# Power_Supply.net
KiCad netlist of a schematic drawn in Altium Designer
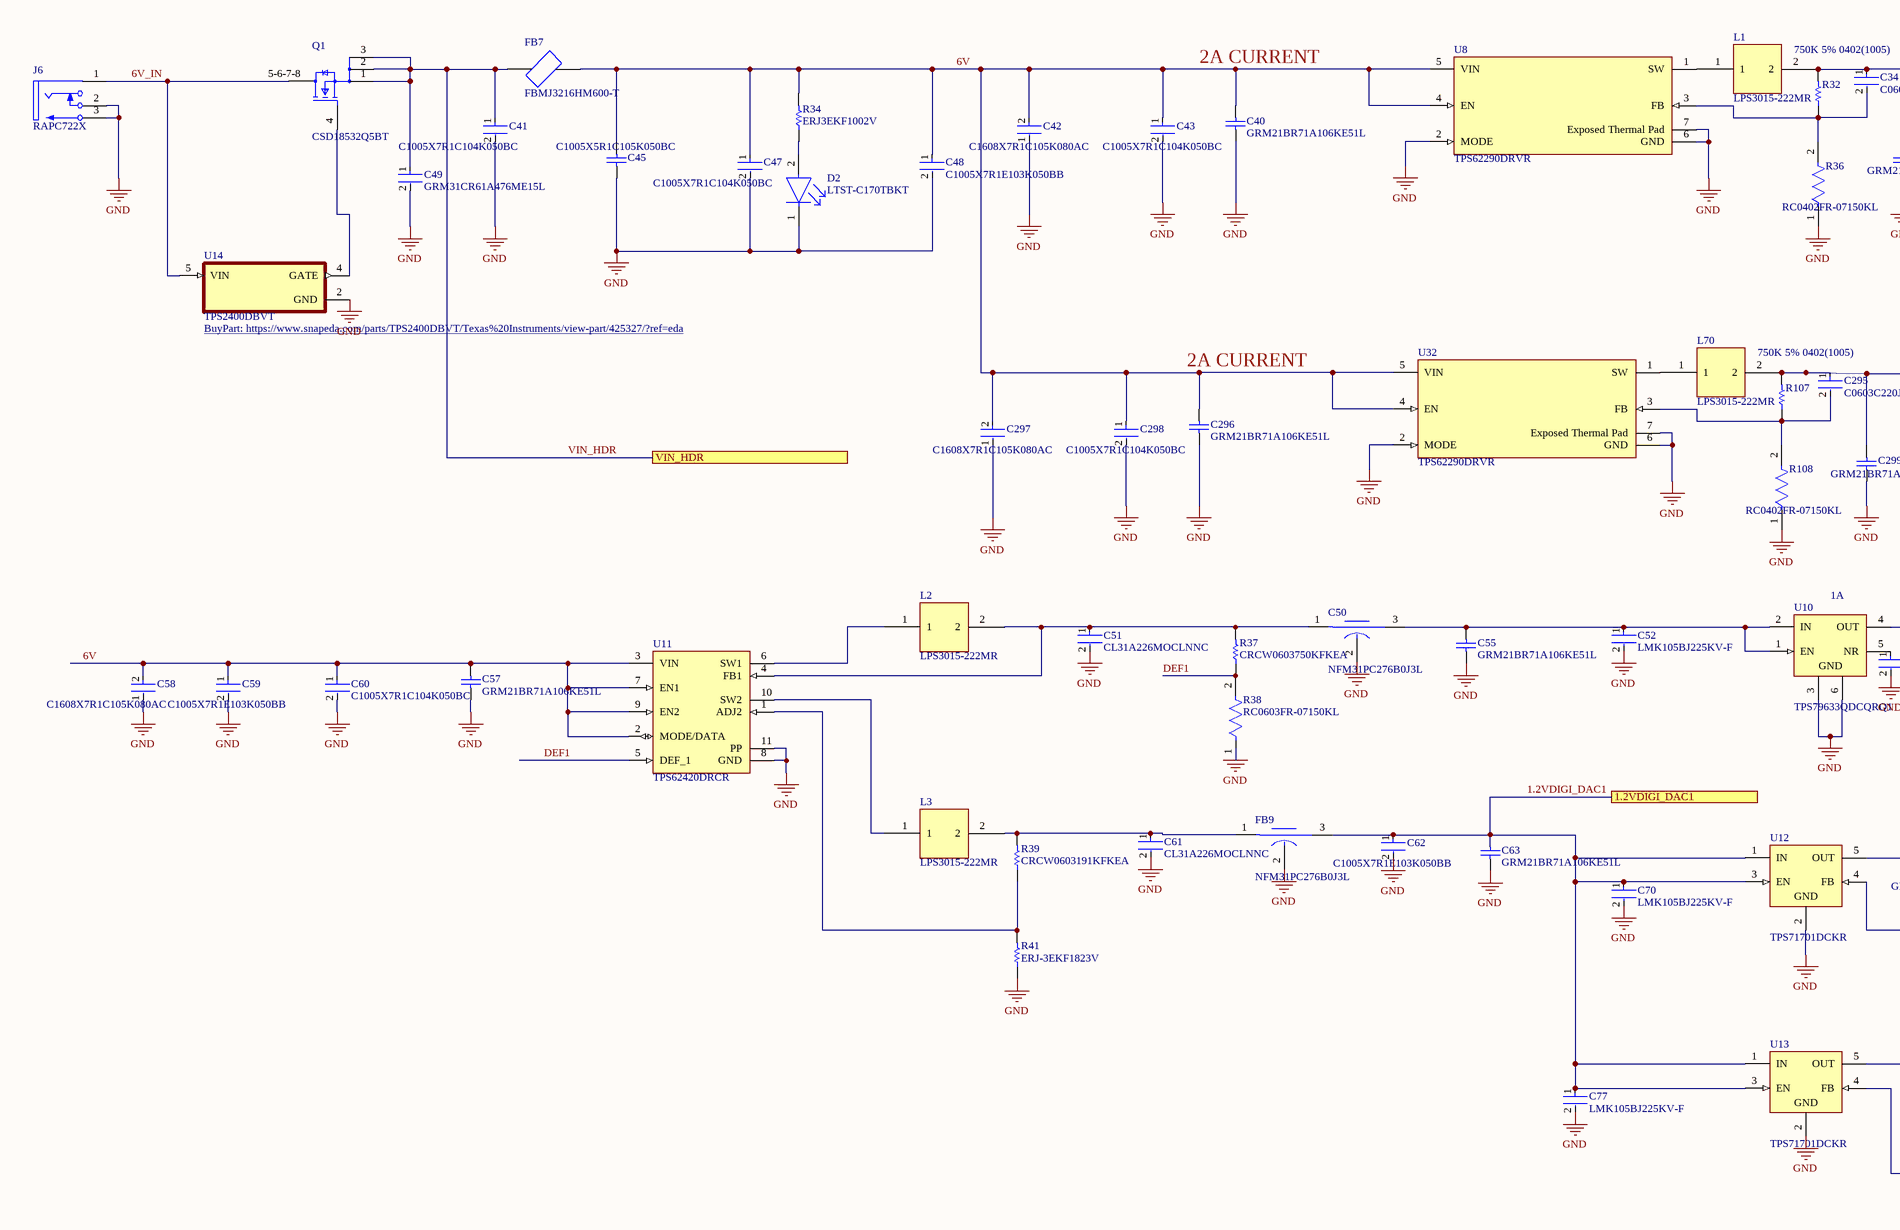
[diagram p0: Power_Supply.SchDoc, top left]
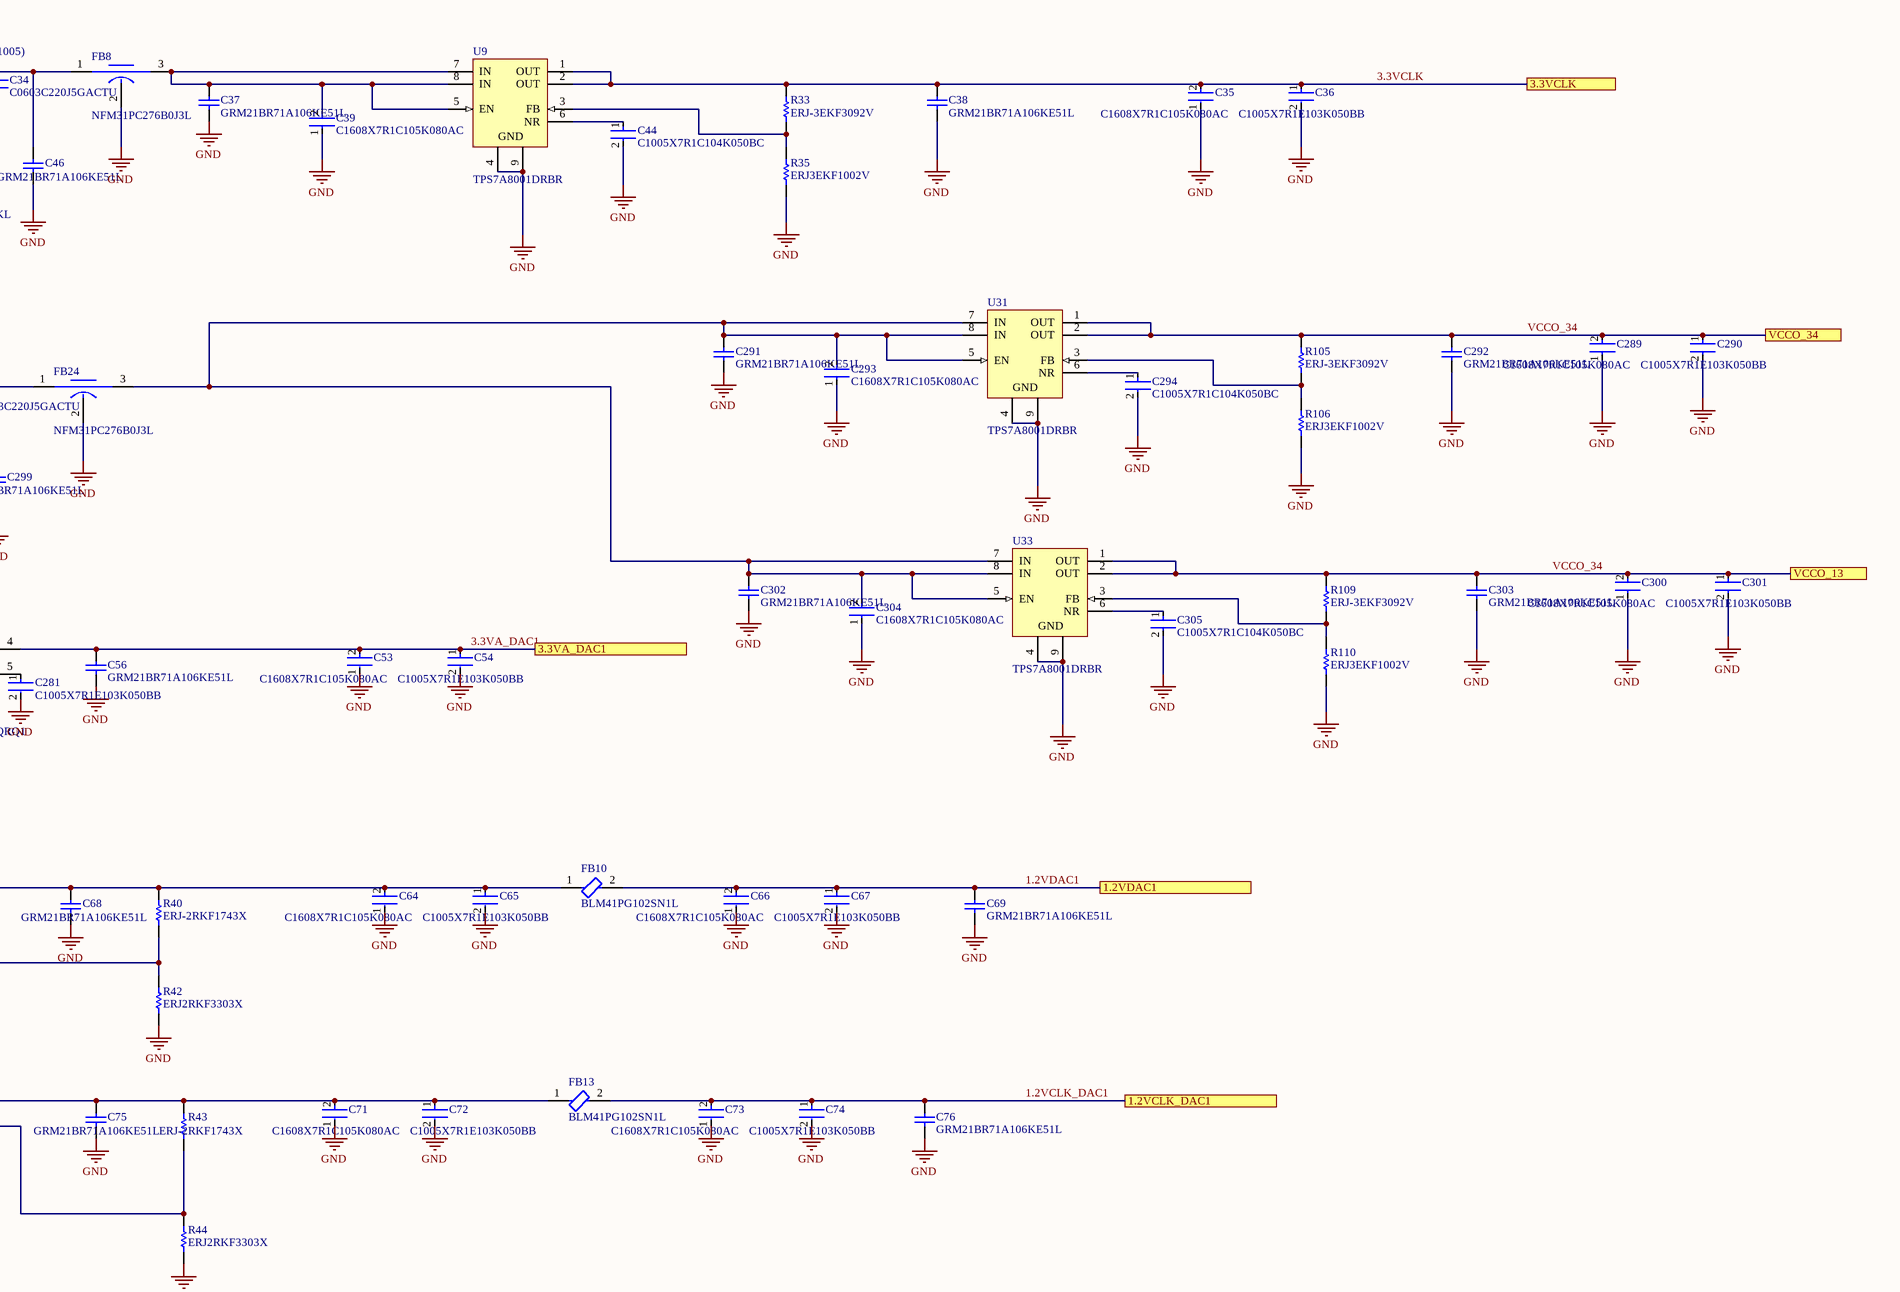
[diagram p1: Power_Supply.SchDoc, top right]
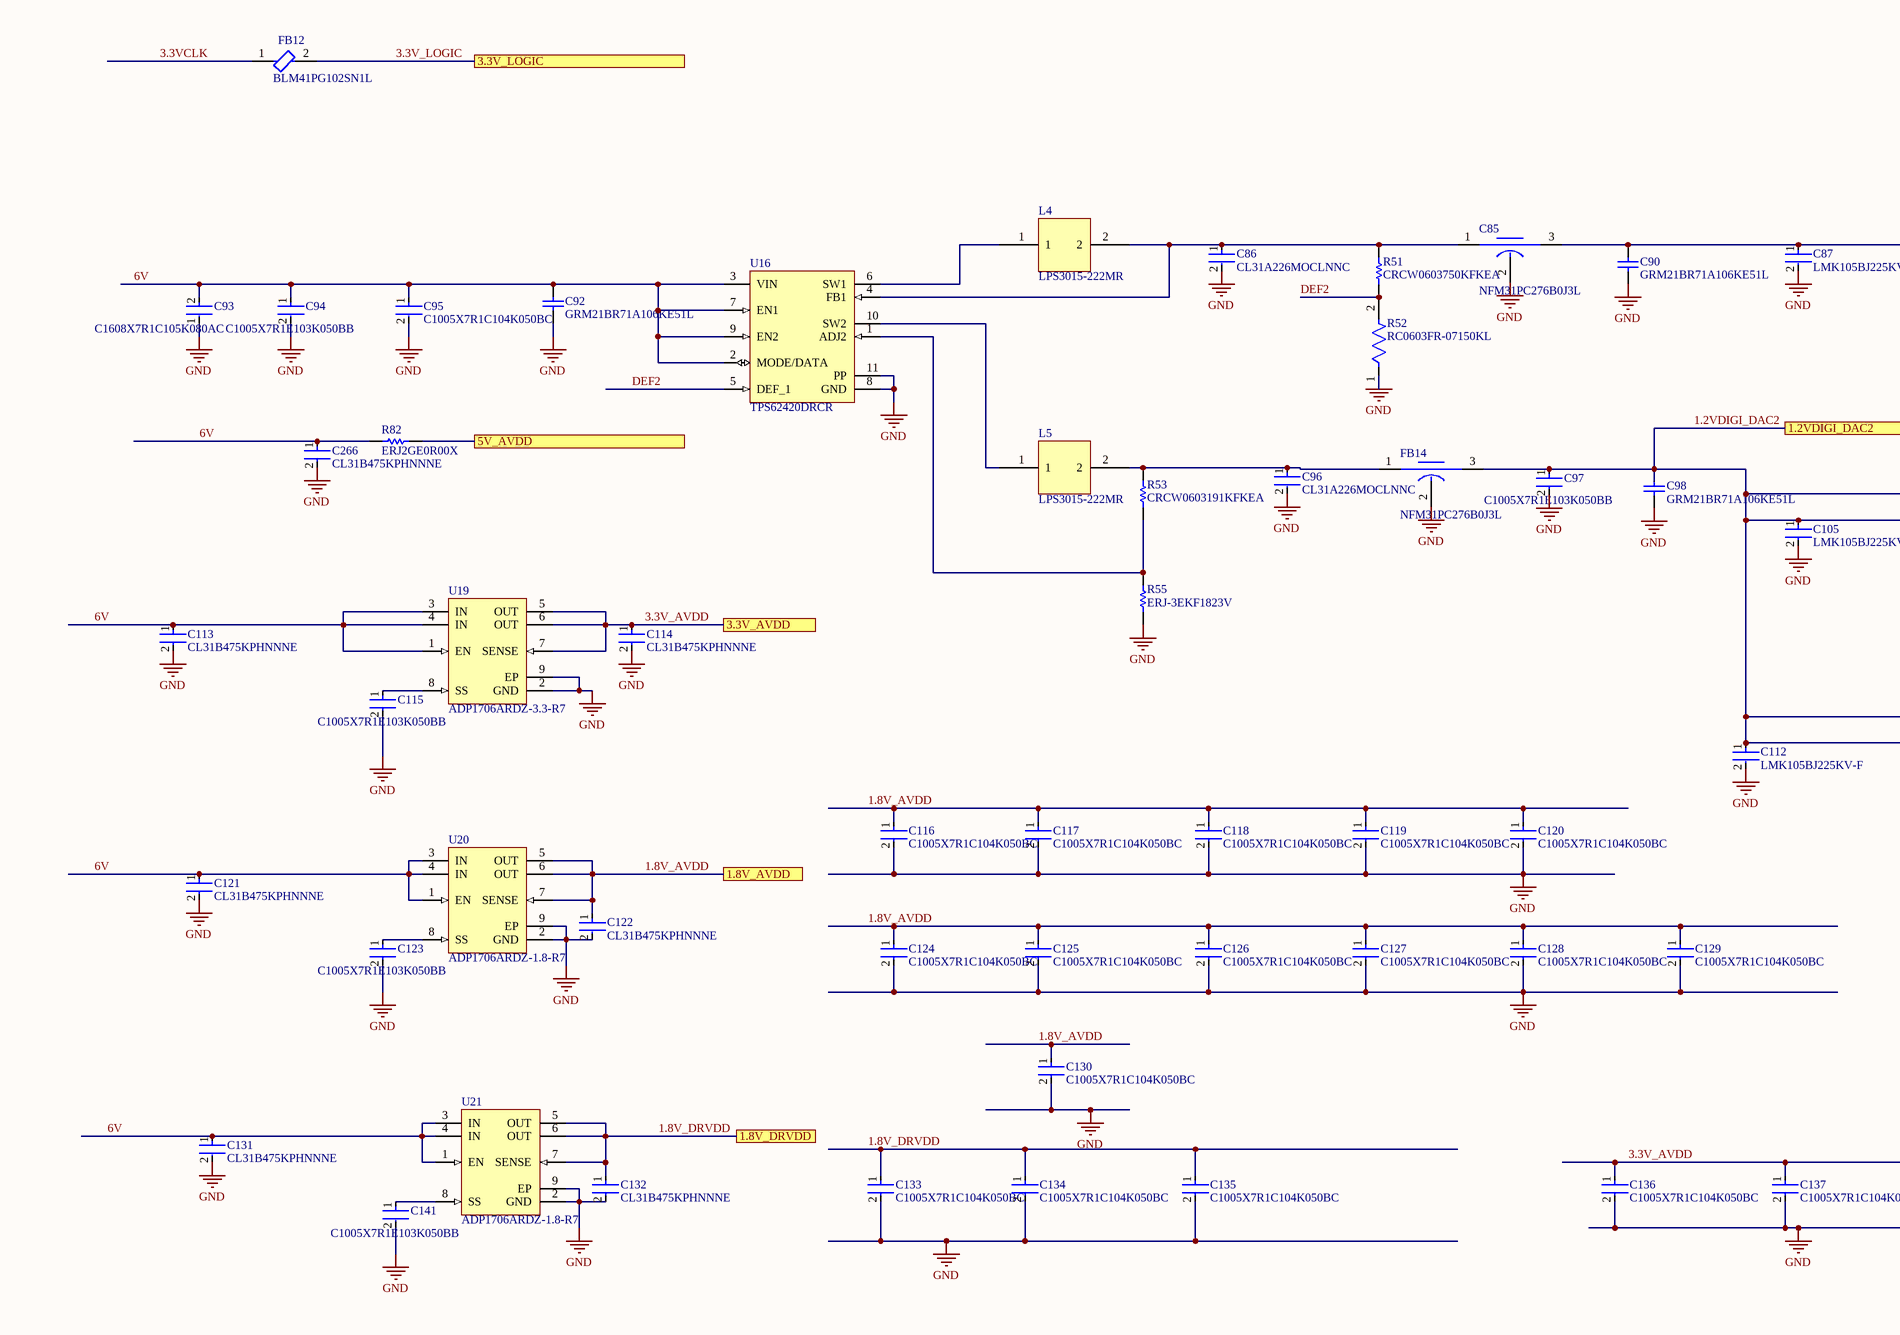
[diagram p2: Power_Supply.SchDoc, bottom left]
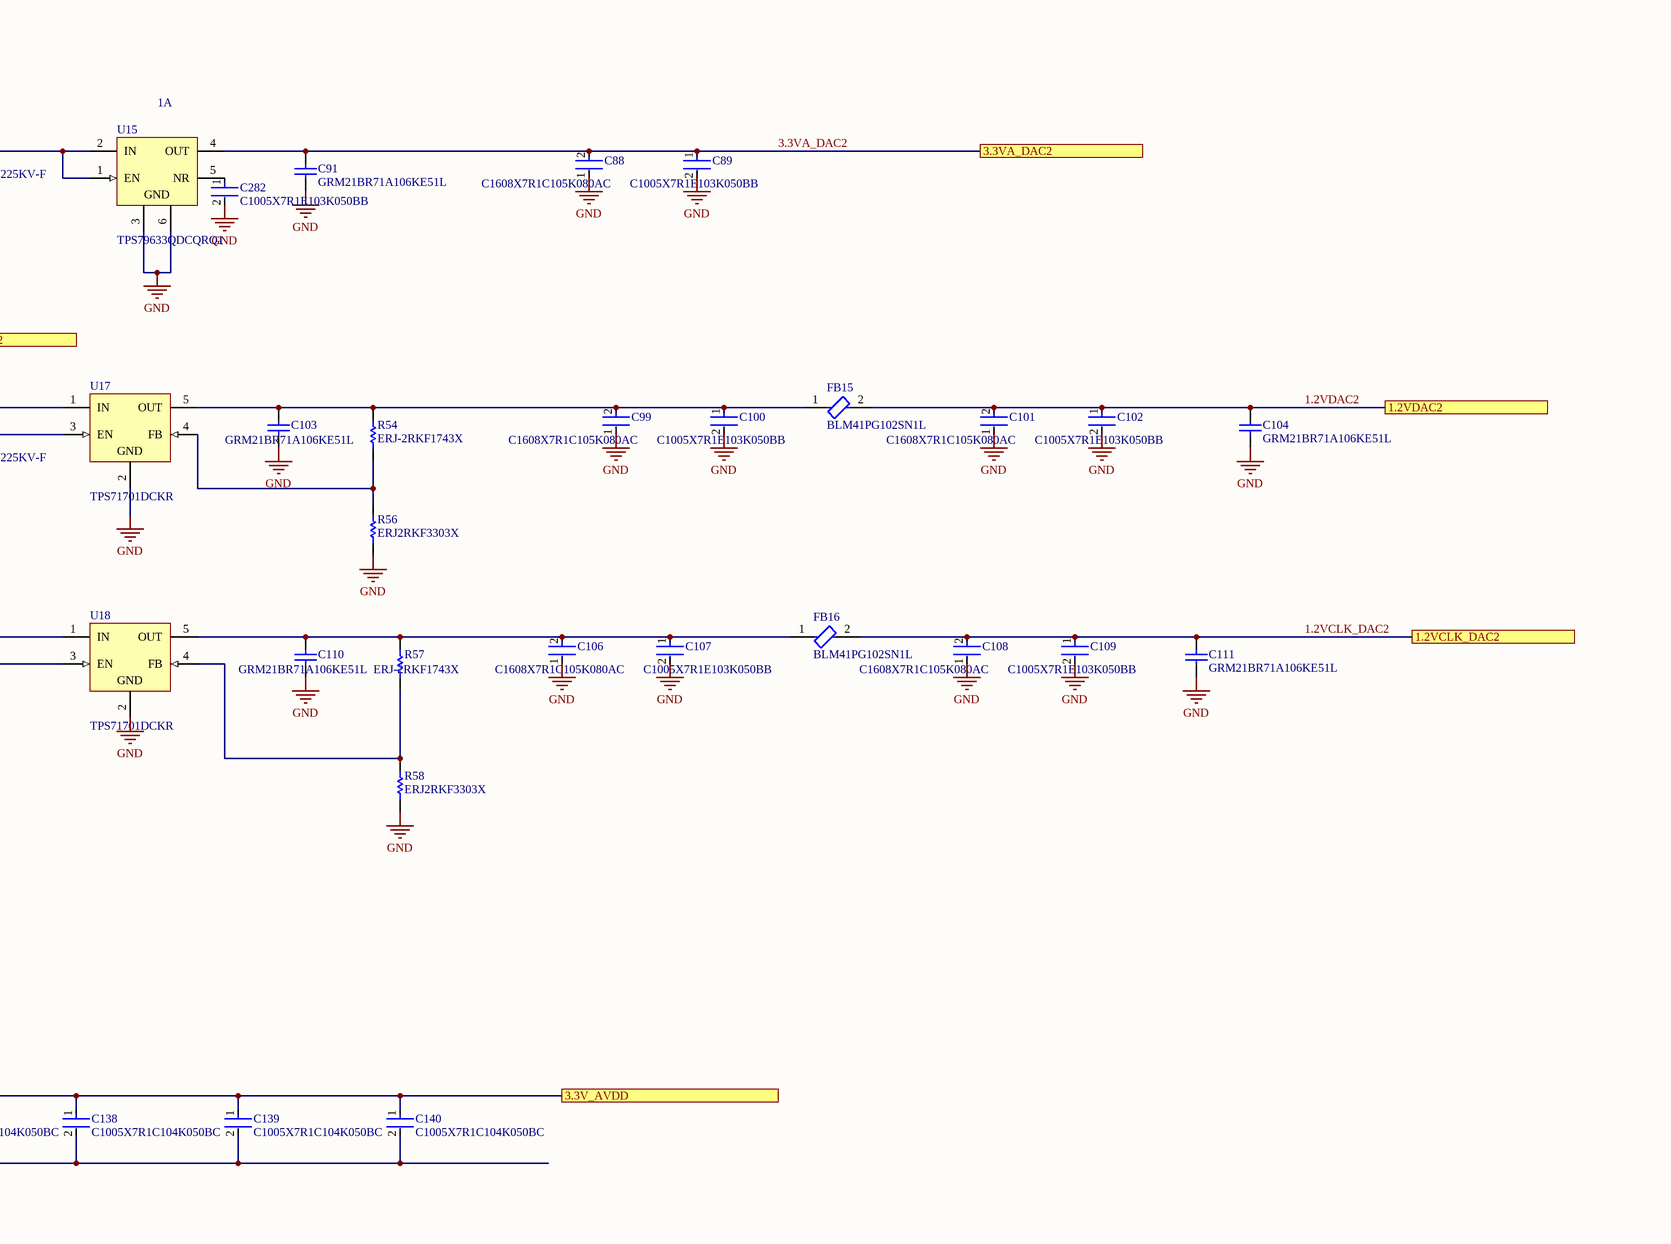
[diagram p3: Power_Supply.SchDoc, bottom right]

(export (version "E")
  (design (tool "Eeschema 10.0.6"))
  (components
    (comp (ref "C34")
      (value "C0603C220J5GACTU")
      (footprint "C0603")
      (description "Cap Ceramic 22pF 50V C0G 5% SMD 0603 125°C Paper T/R")
      (fields (field (name "TOLERANCE") "0.05") (field (name "MANUFACTURER") "KEMET"))
      (libsource (lib "DACֹֹ_Sources") (part "b4654b650e69147ec39a6b967a45e02"))
    )
    (comp (ref "C35")
      (value "C1608X7R1C105K080AC")
      (footprint "C0603")
      (description "Multilayer Ceramic Capacitors 1μF ±10% 16V X7R SMD 0603")
      (fields (field (name "VOLTAGE") "16V") (field (name "TOLERANCE") "10%"))
      (libsource (lib "DACֹֹ_Sources") (part "236180d848d6139a670b325ea6854c9"))
    )
    (comp (ref "C36")
      (value "C1005X7R1E103K050BB")
      (footprint "C0402")
      (description "Multilayer Ceramic Capacitors 10nF ±10% 25V X7R SMD 0402")
      (fields (field (name "TOLERANCE") "10%") (field (name "VOLTAGE") "25V"))
      (libsource (lib "DACֹֹ_Sources") (part "b4654b650e69147ec39a6b967a45e02"))
    )
    (comp (ref "C37")
      (value "GRM21BR71A106KE51L")
      (footprint "C0805")
      (fields (field (name "MANUFACTURER") "Murata"))
      (libsource (lib "DACֹֹ_Sources") (part "CAP"))
    )
    (comp (ref "C38")
      (value "GRM21BR71A106KE51L")
      (footprint "C0805")
      (fields (field (name "MANUFACTURER") "Murata"))
      (libsource (lib "DACֹֹ_Sources") (part "CAP"))
    )
    (comp (ref "C39")
      (value "C1608X7R1C105K080AC")
      (footprint "C0603")
      (description "Multilayer Ceramic Capacitors 1μF ±10% 16V X7R SMD 0603")
      (fields (field (name "VOLTAGE") "16V") (field (name "TOLERANCE") "10%"))
      (libsource (lib "DACֹֹ_Sources") (part "236180d848d6139a670b325ea6854c9"))
    )
    (comp (ref "C40")
      (value "GRM21BR71A106KE51L")
      (footprint "C0805")
      (fields (field (name "MANUFACTURER") "Murata"))
      (libsource (lib "DACֹֹ_Sources") (part "CAP"))
    )
    (comp (ref "C41")
      (value "C1005X7R1C104K050BC")
      (footprint "C0402")
      (description "Multilayer Ceramic Capacitors 100nF ±10% 16V X7R SMD 0402")
      (fields (field (name "VOLTAGE") "16V") (field (name "TOLERANCE") "10%"))
      (libsource (lib "DACֹֹ_Sources") (part "b4654b650e69147ec39a6b967a45e02"))
    )
    (comp (ref "C42")
      (value "C1608X7R1C105K080AC")
      (footprint "C0603")
      (description "Multilayer Ceramic Capacitors 1μF ±10% 16V X7R SMD 0603")
      (fields (field (name "VOLTAGE") "16V") (field (name "TOLERANCE") "10%"))
      (libsource (lib "DACֹֹ_Sources") (part "236180d848d6139a670b325ea6854c9"))
    )
    (comp (ref "C43")
      (value "C1005X7R1C104K050BC")
      (footprint "C0402")
      (description "Multilayer Ceramic Capacitors 100nF ±10% 16V X7R SMD 0402")
      (fields (field (name "VOLTAGE") "16V") (field (name "TOLERANCE") "10%"))
      (libsource (lib "DACֹֹ_Sources") (part "b4654b650e69147ec39a6b967a45e02"))
    )
    (comp (ref "C44")
      (value "C1005X7R1C104K050BC")
      (footprint "C0402")
      (description "Multilayer Ceramic Capacitors 100nF ±10% 16V X7R SMD 0402")
      (fields (field (name "VOLTAGE") "16V") (field (name "TOLERANCE") "10%"))
      (libsource (lib "DACֹֹ_Sources") (part "b4654b650e69147ec39a6b967a45e02"))
    )
    (comp (ref "C45")
      (value "C1005X5R1C105K050BC")
      (footprint "C0402")
      (description "Chip Capacitor, 1 uF, +/- 10%, 16 V, -55 to 85 degC, 0402 (1005 Metric), RoHS, Tape and Reel")
      (fields
        (field (name "TOLERANCE") "±10%")
        (field (name "PCN PART NUMBER") "MLCCPartNumberChange30/Nov/2012")
      )
      (libsource (lib "DACֹֹ_Sources") (part "CAP-NP-2"))
    )
    (comp (ref "C46")
      (value "GRM21BR71A106KE51L")
      (footprint "C0805")
      (fields (field (name "MANUFACTURER") "Murata"))
      (libsource (lib "DACֹֹ_Sources") (part "CAP"))
    )
    (comp (ref "C47")
      (value "C1005X7R1C104K050BC")
      (footprint "C0402")
      (description "Multilayer Ceramic Capacitors 100nF ±10% 16V X7R SMD 0402")
      (fields (field (name "VOLTAGE") "16V") (field (name "TOLERANCE") "10%"))
      (libsource (lib "DACֹֹ_Sources") (part "b4654b650e69147ec39a6b967a45e02"))
    )
    (comp (ref "C48")
      (value "C1005X7R1E103K050BB")
      (footprint "C0402")
      (description "Multilayer Ceramic Capacitors 10nF ±10% 25V X7R SMD 0402")
      (fields (field (name "TOLERANCE") "10%") (field (name "VOLTAGE") "25V"))
      (libsource (lib "DACֹֹ_Sources") (part "b4654b650e69147ec39a6b967a45e02"))
    )
    (comp (ref "C49")
      (value "GRM31CR61A476ME15L")
      (footprint "C1206")
      (description "Chip Multilayer Ceramic Capacitors for General Purpose, 1206, 47uF, X5R, 15%, 20%, 10V")
      (fields (field (name "TOLERANCE") "20%") (field (name "VOLTAGE") "10V"))
      (libsource (lib "DACֹֹ_Sources") (part "02cd4be3c70576c341d710602a673aa"))
    )
    (comp (ref "C50")
      (value "NFM31PC276B0J3L")
      (footprint "FP-NFM31-0_2-MFG")
      (fields (field (name "VOLTAGE") "6.3V") (field (name "TOLERANCE") "20%"))
      (libsource (lib "DACֹֹ_Sources") (part "968ca41a07abfef6fd4f7114a56c54f"))
    )
    (comp (ref "C51")
      (value "CL31A226MOCLNNC")
      (footprint "C1206")
      (description "Cap Ceramic 22uF 16V X5R ±20% SMD 1206 +85°C Embossed T/R")
      (fields (field (name "TOLERANCE") "20%") (field (name "VOLTAGE") "16V"))
      (libsource (lib "DACֹֹ_Sources") (part "b4654b650e69147ec39a6b967a45e02"))
    )
    (comp (ref "C52")
      (value "LMK105BJ225KV-F")
      (footprint "C0402")
      (description "None")
      (fields (field (name "TOLERANCE") "10%"))
      (libsource (lib "DACֹֹ_Sources") (part "b4654b650e69147ec39a6b967a45e02"))
    )
    (comp (ref "C53")
      (value "C1608X7R1C105K080AC")
      (footprint "C0603")
      (description "Multilayer Ceramic Capacitors 1μF ±10% 16V X7R SMD 0603")
      (fields (field (name "VOLTAGE") "16V") (field (name "TOLERANCE") "10%"))
      (libsource (lib "DACֹֹ_Sources") (part "236180d848d6139a670b325ea6854c9"))
    )
    (comp (ref "C54")
      (value "C1005X7R1E103K050BB")
      (footprint "C0402")
      (description "Multilayer Ceramic Capacitors 10nF ±10% 25V X7R SMD 0402")
      (fields (field (name "TOLERANCE") "10%") (field (name "VOLTAGE") "25V"))
      (libsource (lib "DACֹֹ_Sources") (part "b4654b650e69147ec39a6b967a45e02"))
    )
    (comp (ref "C55")
      (value "GRM21BR71A106KE51L")
      (footprint "C0805")
      (fields (field (name "MANUFACTURER") "Murata"))
      (libsource (lib "DACֹֹ_Sources") (part "CAP"))
    )
    (comp (ref "C56")
      (value "GRM21BR71A106KE51L")
      (footprint "C0805")
      (fields (field (name "MANUFACTURER") "Murata"))
      (libsource (lib "DACֹֹ_Sources") (part "CAP"))
    )
    (comp (ref "C57")
      (value "GRM21BR71A106KE51L")
      (footprint "C0805")
      (fields (field (name "MANUFACTURER") "Murata"))
      (libsource (lib "DACֹֹ_Sources") (part "CAP"))
    )
    (comp (ref "C58")
      (value "C1608X7R1C105K080AC")
      (footprint "C0603")
      (description "Multilayer Ceramic Capacitors 1μF ±10% 16V X7R SMD 0603")
      (fields (field (name "VOLTAGE") "16V") (field (name "TOLERANCE") "10%"))
      (libsource (lib "DACֹֹ_Sources") (part "236180d848d6139a670b325ea6854c9"))
    )
    (comp (ref "C59")
      (value "C1005X7R1E103K050BB")
      (footprint "C0402")
      (description "Multilayer Ceramic Capacitors 10nF ±10% 25V X7R SMD 0402")
      (fields (field (name "TOLERANCE") "10%") (field (name "VOLTAGE") "25V"))
      (libsource (lib "DACֹֹ_Sources") (part "b4654b650e69147ec39a6b967a45e02"))
    )
    (comp (ref "C60")
      (value "C1005X7R1C104K050BC")
      (footprint "C0402")
      (description "Multilayer Ceramic Capacitors 100nF ±10% 16V X7R SMD 0402")
      (fields (field (name "VOLTAGE") "16V") (field (name "TOLERANCE") "10%"))
      (libsource (lib "DACֹֹ_Sources") (part "b4654b650e69147ec39a6b967a45e02"))
    )
    (comp (ref "C61")
      (value "CL31A226MOCLNNC")
      (footprint "C1206")
      (description "Cap Ceramic 22uF 16V X5R ±20% SMD 1206 +85°C Embossed T/R")
      (fields (field (name "TOLERANCE") "20%") (field (name "VOLTAGE") "16V"))
      (libsource (lib "DACֹֹ_Sources") (part "b4654b650e69147ec39a6b967a45e02"))
    )
    (comp (ref "C62")
      (value "C1005X7R1E103K050BB")
      (footprint "C0402")
      (description "Multilayer Ceramic Capacitors 10nF ±10% 25V X7R SMD 0402")
      (fields (field (name "TOLERANCE") "10%") (field (name "VOLTAGE") "25V"))
      (libsource (lib "DACֹֹ_Sources") (part "b4654b650e69147ec39a6b967a45e02"))
    )
    (comp (ref "C63")
      (value "GRM21BR71A106KE51L")
      (footprint "C0805")
      (fields (field (name "MANUFACTURER") "Murata"))
      (libsource (lib "DACֹֹ_Sources") (part "CAP"))
    )
    (comp (ref "C64")
      (value "C1608X7R1C105K080AC")
      (footprint "C0603")
      (description "Multilayer Ceramic Capacitors 1μF ±10% 16V X7R SMD 0603")
      (fields (field (name "VOLTAGE") "16V") (field (name "TOLERANCE") "10%"))
      (libsource (lib "DACֹֹ_Sources") (part "236180d848d6139a670b325ea6854c9"))
    )
    (comp (ref "C65")
      (value "C1005X7R1E103K050BB")
      (footprint "C0402")
      (description "Multilayer Ceramic Capacitors 10nF ±10% 25V X7R SMD 0402")
      (fields (field (name "TOLERANCE") "10%") (field (name "VOLTAGE") "25V"))
      (libsource (lib "DACֹֹ_Sources") (part "b4654b650e69147ec39a6b967a45e02"))
    )
    (comp (ref "C66")
      (value "C1608X7R1C105K080AC")
      (footprint "C0603")
      (description "Multilayer Ceramic Capacitors 1μF ±10% 16V X7R SMD 0603")
      (fields (field (name "VOLTAGE") "16V") (field (name "TOLERANCE") "10%"))
      (libsource (lib "DACֹֹ_Sources") (part "236180d848d6139a670b325ea6854c9"))
    )
    (comp (ref "C67")
      (value "C1005X7R1E103K050BB")
      (footprint "C0402")
      (description "Multilayer Ceramic Capacitors 10nF ±10% 25V X7R SMD 0402")
      (fields (field (name "TOLERANCE") "10%") (field (name "VOLTAGE") "25V"))
      (libsource (lib "DACֹֹ_Sources") (part "b4654b650e69147ec39a6b967a45e02"))
    )
    (comp (ref "C68")
      (value "GRM21BR71A106KE51L")
      (footprint "C0805")
      (fields (field (name "MANUFACTURER") "Murata"))
      (libsource (lib "DACֹֹ_Sources") (part "CAP"))
    )
    (comp (ref "C69")
      (value "GRM21BR71A106KE51L")
      (footprint "C0805")
      (fields (field (name "MANUFACTURER") "Murata"))
      (libsource (lib "DACֹֹ_Sources") (part "CAP"))
    )
    (comp (ref "C70")
      (value "LMK105BJ225KV-F")
      (footprint "C0402")
      (description "None")
      (fields (field (name "TOLERANCE") "10%"))
      (libsource (lib "DACֹֹ_Sources") (part "b4654b650e69147ec39a6b967a45e02"))
    )
    (comp (ref "C71")
      (value "C1608X7R1C105K080AC")
      (footprint "C0603")
      (description "Multilayer Ceramic Capacitors 1μF ±10% 16V X7R SMD 0603")
      (fields (field (name "VOLTAGE") "16V") (field (name "TOLERANCE") "10%"))
      (libsource (lib "DACֹֹ_Sources") (part "236180d848d6139a670b325ea6854c9"))
    )
    (comp (ref "C72")
      (value "C1005X7R1E103K050BB")
      (footprint "C0402")
      (description "Multilayer Ceramic Capacitors 10nF ±10% 25V X7R SMD 0402")
      (fields (field (name "TOLERANCE") "10%") (field (name "VOLTAGE") "25V"))
      (libsource (lib "DACֹֹ_Sources") (part "b4654b650e69147ec39a6b967a45e02"))
    )
    (comp (ref "C73")
      (value "C1608X7R1C105K080AC")
      (footprint "C0603")
      (description "Multilayer Ceramic Capacitors 1μF ±10% 16V X7R SMD 0603")
      (fields (field (name "VOLTAGE") "16V") (field (name "TOLERANCE") "10%"))
      (libsource (lib "DACֹֹ_Sources") (part "236180d848d6139a670b325ea6854c9"))
    )
    (comp (ref "C74")
      (value "C1005X7R1E103K050BB")
      (footprint "C0402")
      (description "Multilayer Ceramic Capacitors 10nF ±10% 25V X7R SMD 0402")
      (fields (field (name "TOLERANCE") "10%") (field (name "VOLTAGE") "25V"))
      (libsource (lib "DACֹֹ_Sources") (part "b4654b650e69147ec39a6b967a45e02"))
    )
    (comp (ref "C75")
      (value "GRM21BR71A106KE51L")
      (footprint "C0805")
      (fields (field (name "MANUFACTURER") "Murata"))
      (libsource (lib "DACֹֹ_Sources") (part "CAP"))
    )
    (comp (ref "C76")
      (value "GRM21BR71A106KE51L")
      (footprint "C0805")
      (fields (field (name "MANUFACTURER") "Murata"))
      (libsource (lib "DACֹֹ_Sources") (part "CAP"))
    )
    (comp (ref "C77")
      (value "LMK105BJ225KV-F")
      (footprint "C0402")
      (description "None")
      (fields (field (name "TOLERANCE") "10%"))
      (libsource (lib "DACֹֹ_Sources") (part "b4654b650e69147ec39a6b967a45e02"))
    )
    (comp (ref "C85")
      (value "NFM31PC276B0J3L")
      (footprint "FP-NFM31-0_2-MFG")
      (fields (field (name "VOLTAGE") "6.3V") (field (name "TOLERANCE") "20%"))
      (libsource (lib "DACֹֹ_Sources") (part "968ca41a07abfef6fd4f7114a56c54f"))
    )
    (comp (ref "C86")
      (value "CL31A226MOCLNNC")
      (footprint "C1206")
      (description "Cap Ceramic 22uF 16V X5R ±20% SMD 1206 +85°C Embossed T/R")
      (fields (field (name "TOLERANCE") "20%") (field (name "VOLTAGE") "16V"))
      (libsource (lib "DACֹֹ_Sources") (part "b4654b650e69147ec39a6b967a45e02"))
    )
    (comp (ref "C87")
      (value "LMK105BJ225KV-F")
      (footprint "C0402")
      (description "None")
      (fields (field (name "TOLERANCE") "10%"))
      (libsource (lib "DACֹֹ_Sources") (part "b4654b650e69147ec39a6b967a45e02"))
    )
    (comp (ref "C88")
      (value "C1608X7R1C105K080AC")
      (footprint "C0603")
      (description "Multilayer Ceramic Capacitors 1μF ±10% 16V X7R SMD 0603")
      (fields (field (name "VOLTAGE") "16V") (field (name "TOLERANCE") "10%"))
      (libsource (lib "DACֹֹ_Sources") (part "236180d848d6139a670b325ea6854c9"))
    )
    (comp (ref "C89")
      (value "C1005X7R1E103K050BB")
      (footprint "C0402")
      (description "Multilayer Ceramic Capacitors 10nF ±10% 25V X7R SMD 0402")
      (fields (field (name "TOLERANCE") "10%") (field (name "VOLTAGE") "25V"))
      (libsource (lib "DACֹֹ_Sources") (part "b4654b650e69147ec39a6b967a45e02"))
    )
    (comp (ref "C90")
      (value "GRM21BR71A106KE51L")
      (footprint "C0805")
      (fields (field (name "MANUFACTURER") "Murata"))
      (libsource (lib "DACֹֹ_Sources") (part "CAP"))
    )
    (comp (ref "C91")
      (value "GRM21BR71A106KE51L")
      (footprint "C0805")
      (fields (field (name "MANUFACTURER") "Murata"))
      (libsource (lib "DACֹֹ_Sources") (part "CAP"))
    )
    (comp (ref "C92")
      (value "GRM21BR71A106KE51L")
      (footprint "C0805")
      (fields (field (name "MANUFACTURER") "Murata"))
      (libsource (lib "DACֹֹ_Sources") (part "CAP"))
    )
    (comp (ref "C93")
      (value "C1608X7R1C105K080AC")
      (footprint "C0603")
      (description "Multilayer Ceramic Capacitors 1μF ±10% 16V X7R SMD 0603")
      (fields (field (name "VOLTAGE") "16V") (field (name "TOLERANCE") "10%"))
      (libsource (lib "DACֹֹ_Sources") (part "236180d848d6139a670b325ea6854c9"))
    )
    (comp (ref "C94")
      (value "C1005X7R1E103K050BB")
      (footprint "C0402")
      (description "Multilayer Ceramic Capacitors 10nF ±10% 25V X7R SMD 0402")
      (fields (field (name "TOLERANCE") "10%") (field (name "VOLTAGE") "25V"))
      (libsource (lib "DACֹֹ_Sources") (part "b4654b650e69147ec39a6b967a45e02"))
    )
    (comp (ref "C95")
      (value "C1005X7R1C104K050BC")
      (footprint "C0402")
      (description "Multilayer Ceramic Capacitors 100nF ±10% 16V X7R SMD 0402")
      (fields (field (name "VOLTAGE") "16V") (field (name "TOLERANCE") "10%"))
      (libsource (lib "DACֹֹ_Sources") (part "b4654b650e69147ec39a6b967a45e02"))
    )
    (comp (ref "C96")
      (value "CL31A226MOCLNNC")
      (footprint "C1206")
      (description "Cap Ceramic 22uF 16V X5R ±20% SMD 1206 +85°C Embossed T/R")
      (fields (field (name "TOLERANCE") "20%") (field (name "VOLTAGE") "16V"))
      (libsource (lib "DACֹֹ_Sources") (part "b4654b650e69147ec39a6b967a45e02"))
    )
    (comp (ref "C97")
      (value "C1005X7R1E103K050BB")
      (footprint "C0402")
      (description "Multilayer Ceramic Capacitors 10nF ±10% 25V X7R SMD 0402")
      (fields (field (name "TOLERANCE") "10%") (field (name "VOLTAGE") "25V"))
      (libsource (lib "DACֹֹ_Sources") (part "b4654b650e69147ec39a6b967a45e02"))
    )
    (comp (ref "C98")
      (value "GRM21BR71A106KE51L")
      (footprint "C0805")
      (fields (field (name "MANUFACTURER") "Murata"))
      (libsource (lib "DACֹֹ_Sources") (part "CAP"))
    )
    (comp (ref "C99")
      (value "C1608X7R1C105K080AC")
      (footprint "C0603")
      (description "Multilayer Ceramic Capacitors 1μF ±10% 16V X7R SMD 0603")
      (fields (field (name "VOLTAGE") "16V") (field (name "TOLERANCE") "10%"))
      (libsource (lib "DACֹֹ_Sources") (part "236180d848d6139a670b325ea6854c9"))
    )
    (comp (ref "C100")
      (value "C1005X7R1E103K050BB")
      (footprint "C0402")
      (description "Multilayer Ceramic Capacitors 10nF ±10% 25V X7R SMD 0402")
      (fields (field (name "TOLERANCE") "10%") (field (name "VOLTAGE") "25V"))
      (libsource (lib "DACֹֹ_Sources") (part "b4654b650e69147ec39a6b967a45e02"))
    )
    (comp (ref "C101")
      (value "C1608X7R1C105K080AC")
      (footprint "C0603")
      (description "Multilayer Ceramic Capacitors 1μF ±10% 16V X7R SMD 0603")
      (fields (field (name "VOLTAGE") "16V") (field (name "TOLERANCE") "10%"))
      (libsource (lib "DACֹֹ_Sources") (part "236180d848d6139a670b325ea6854c9"))
    )
    (comp (ref "C102")
      (value "C1005X7R1E103K050BB")
      (footprint "C0402")
      (description "Multilayer Ceramic Capacitors 10nF ±10% 25V X7R SMD 0402")
      (fields (field (name "TOLERANCE") "10%") (field (name "VOLTAGE") "25V"))
      (libsource (lib "DACֹֹ_Sources") (part "b4654b650e69147ec39a6b967a45e02"))
    )
    (comp (ref "C103")
      (value "GRM21BR71A106KE51L")
      (footprint "C0805")
      (fields (field (name "MANUFACTURER") "Murata"))
      (libsource (lib "DACֹֹ_Sources") (part "CAP"))
    )
    (comp (ref "C104")
      (value "GRM21BR71A106KE51L")
      (footprint "C0805")
      (fields (field (name "MANUFACTURER") "Murata"))
      (libsource (lib "DACֹֹ_Sources") (part "CAP"))
    )
    (comp (ref "C105")
      (value "LMK105BJ225KV-F")
      (footprint "C0402")
      (description "None")
      (fields (field (name "TOLERANCE") "10%"))
      (libsource (lib "DACֹֹ_Sources") (part "b4654b650e69147ec39a6b967a45e02"))
    )
    (comp (ref "C106")
      (value "C1608X7R1C105K080AC")
      (footprint "C0603")
      (description "Multilayer Ceramic Capacitors 1μF ±10% 16V X7R SMD 0603")
      (fields (field (name "VOLTAGE") "16V") (field (name "TOLERANCE") "10%"))
      (libsource (lib "DACֹֹ_Sources") (part "236180d848d6139a670b325ea6854c9"))
    )
    (comp (ref "C107")
      (value "C1005X7R1E103K050BB")
      (footprint "C0402")
      (description "Multilayer Ceramic Capacitors 10nF ±10% 25V X7R SMD 0402")
      (fields (field (name "TOLERANCE") "10%") (field (name "VOLTAGE") "25V"))
      (libsource (lib "DACֹֹ_Sources") (part "b4654b650e69147ec39a6b967a45e02"))
    )
    (comp (ref "C108")
      (value "C1608X7R1C105K080AC")
      (footprint "C0603")
      (description "Multilayer Ceramic Capacitors 1μF ±10% 16V X7R SMD 0603")
      (fields (field (name "VOLTAGE") "16V") (field (name "TOLERANCE") "10%"))
      (libsource (lib "DACֹֹ_Sources") (part "236180d848d6139a670b325ea6854c9"))
    )
    (comp (ref "C109")
      (value "C1005X7R1E103K050BB")
      (footprint "C0402")
      (description "Multilayer Ceramic Capacitors 10nF ±10% 25V X7R SMD 0402")
      (fields (field (name "TOLERANCE") "10%") (field (name "VOLTAGE") "25V"))
      (libsource (lib "DACֹֹ_Sources") (part "b4654b650e69147ec39a6b967a45e02"))
    )
    (comp (ref "C110")
      (value "GRM21BR71A106KE51L")
      (footprint "C0805")
      (fields (field (name "MANUFACTURER") "Murata"))
      (libsource (lib "DACֹֹ_Sources") (part "CAP"))
    )
    (comp (ref "C111")
      (value "GRM21BR71A106KE51L")
      (footprint "C0805")
      (fields (field (name "MANUFACTURER") "Murata"))
      (libsource (lib "DACֹֹ_Sources") (part "CAP"))
    )
    (comp (ref "C112")
      (value "LMK105BJ225KV-F")
      (footprint "C0402")
      (description "None")
      (fields (field (name "TOLERANCE") "10%"))
      (libsource (lib "DACֹֹ_Sources") (part "b4654b650e69147ec39a6b967a45e02"))
    )
    (comp (ref "C113")
      (value "CL31B475KPHNNNE")
      (footprint "C1206")
      (description "Cap Ceramic 4.7uF 10V X7R ±10% SMD 1206 +125°C Embossed T/R")
      (fields (field (name "TOLERANCE") "10%") (field (name "VOLTAGE") "10V"))
      (libsource (lib "DACֹֹ_Sources") (part "b4654b650e69147ec39a6b967a45e02"))
    )
    (comp (ref "C114")
      (value "CL31B475KPHNNNE")
      (footprint "C1206")
      (description "Cap Ceramic 4.7uF 10V X7R ±10% SMD 1206 +125°C Embossed T/R")
      (fields (field (name "TOLERANCE") "10%") (field (name "VOLTAGE") "10V"))
      (libsource (lib "DACֹֹ_Sources") (part "b4654b650e69147ec39a6b967a45e02"))
    )
    (comp (ref "C115")
      (value "C1005X7R1E103K050BB")
      (footprint "C0402")
      (description "Multilayer Ceramic Capacitors 10nF ±10% 25V X7R SMD 0402")
      (fields (field (name "TOLERANCE") "10%") (field (name "VOLTAGE") "25V"))
      (libsource (lib "DACֹֹ_Sources") (part "b4654b650e69147ec39a6b967a45e02"))
    )
    (comp (ref "C116")
      (value "C1005X7R1C104K050BC")
      (footprint "C0402")
      (description "Multilayer Ceramic Capacitors 100nF ±10% 16V X7R SMD 0402")
      (fields (field (name "VOLTAGE") "16V") (field (name "TOLERANCE") "10%"))
      (libsource (lib "DACֹֹ_Sources") (part "b4654b650e69147ec39a6b967a45e02"))
    )
    (comp (ref "C117")
      (value "C1005X7R1C104K050BC")
      (footprint "C0402")
      (description "Multilayer Ceramic Capacitors 100nF ±10% 16V X7R SMD 0402")
      (fields (field (name "VOLTAGE") "16V") (field (name "TOLERANCE") "10%"))
      (libsource (lib "DACֹֹ_Sources") (part "b4654b650e69147ec39a6b967a45e02"))
    )
    (comp (ref "C118")
      (value "C1005X7R1C104K050BC")
      (footprint "C0402")
      (description "Multilayer Ceramic Capacitors 100nF ±10% 16V X7R SMD 0402")
      (fields (field (name "VOLTAGE") "16V") (field (name "TOLERANCE") "10%"))
      (libsource (lib "DACֹֹ_Sources") (part "b4654b650e69147ec39a6b967a45e02"))
    )
    (comp (ref "C119")
      (value "C1005X7R1C104K050BC")
      (footprint "C0402")
      (description "Multilayer Ceramic Capacitors 100nF ±10% 16V X7R SMD 0402")
      (fields (field (name "VOLTAGE") "16V") (field (name "TOLERANCE") "10%"))
      (libsource (lib "DACֹֹ_Sources") (part "b4654b650e69147ec39a6b967a45e02"))
    )
    (comp (ref "C120")
      (value "C1005X7R1C104K050BC")
      (footprint "C0402")
      (description "Multilayer Ceramic Capacitors 100nF ±10% 16V X7R SMD 0402")
      (fields (field (name "VOLTAGE") "16V") (field (name "TOLERANCE") "10%"))
      (libsource (lib "DACֹֹ_Sources") (part "b4654b650e69147ec39a6b967a45e02"))
    )
    (comp (ref "C121")
      (value "CL31B475KPHNNNE")
      (footprint "C1206")
      (description "Cap Ceramic 4.7uF 10V X7R ±10% SMD 1206 +125°C Embossed T/R")
      (fields (field (name "TOLERANCE") "10%") (field (name "VOLTAGE") "10V"))
      (libsource (lib "DACֹֹ_Sources") (part "b4654b650e69147ec39a6b967a45e02"))
    )
    (comp (ref "C122")
      (value "CL31B475KPHNNNE")
      (footprint "C1206")
      (description "Cap Ceramic 4.7uF 10V X7R ±10% SMD 1206 +125°C Embossed T/R")
      (fields (field (name "TOLERANCE") "10%") (field (name "VOLTAGE") "10V"))
      (libsource (lib "DACֹֹ_Sources") (part "b4654b650e69147ec39a6b967a45e02"))
    )
    (comp (ref "C123")
      (value "C1005X7R1E103K050BB")
      (footprint "C0402")
      (description "Multilayer Ceramic Capacitors 10nF ±10% 25V X7R SMD 0402")
      (fields (field (name "TOLERANCE") "10%") (field (name "VOLTAGE") "25V"))
      (libsource (lib "DACֹֹ_Sources") (part "b4654b650e69147ec39a6b967a45e02"))
    )
    (comp (ref "C124")
      (value "C1005X7R1C104K050BC")
      (footprint "C0402")
      (description "Multilayer Ceramic Capacitors 100nF ±10% 16V X7R SMD 0402")
      (fields (field (name "VOLTAGE") "16V") (field (name "TOLERANCE") "10%"))
      (libsource (lib "DACֹֹ_Sources") (part "b4654b650e69147ec39a6b967a45e02"))
    )
    (comp (ref "C125")
      (value "C1005X7R1C104K050BC")
      (footprint "C0402")
      (description "Multilayer Ceramic Capacitors 100nF ±10% 16V X7R SMD 0402")
      (fields (field (name "VOLTAGE") "16V") (field (name "TOLERANCE") "10%"))
      (libsource (lib "DACֹֹ_Sources") (part "b4654b650e69147ec39a6b967a45e02"))
    )
    (comp (ref "C126")
      (value "C1005X7R1C104K050BC")
      (footprint "C0402")
      (description "Multilayer Ceramic Capacitors 100nF ±10% 16V X7R SMD 0402")
      (fields (field (name "VOLTAGE") "16V") (field (name "TOLERANCE") "10%"))
      (libsource (lib "DACֹֹ_Sources") (part "b4654b650e69147ec39a6b967a45e02"))
    )
    (comp (ref "C127")
      (value "C1005X7R1C104K050BC")
      (footprint "C0402")
      (description "Multilayer Ceramic Capacitors 100nF ±10% 16V X7R SMD 0402")
      (fields (field (name "VOLTAGE") "16V") (field (name "TOLERANCE") "10%"))
      (libsource (lib "DACֹֹ_Sources") (part "b4654b650e69147ec39a6b967a45e02"))
    )
    (comp (ref "C128")
      (value "C1005X7R1C104K050BC")
      (footprint "C0402")
      (description "Multilayer Ceramic Capacitors 100nF ±10% 16V X7R SMD 0402")
      (fields (field (name "VOLTAGE") "16V") (field (name "TOLERANCE") "10%"))
      (libsource (lib "DACֹֹ_Sources") (part "b4654b650e69147ec39a6b967a45e02"))
    )
    (comp (ref "C129")
      (value "C1005X7R1C104K050BC")
      (footprint "C0402")
      (description "Multilayer Ceramic Capacitors 100nF ±10% 16V X7R SMD 0402")
      (fields (field (name "VOLTAGE") "16V") (field (name "TOLERANCE") "10%"))
      (libsource (lib "DACֹֹ_Sources") (part "b4654b650e69147ec39a6b967a45e02"))
    )
    (comp (ref "C130")
      (value "C1005X7R1C104K050BC")
      (footprint "C0402")
      (description "Multilayer Ceramic Capacitors 100nF ±10% 16V X7R SMD 0402")
      (fields (field (name "VOLTAGE") "16V") (field (name "TOLERANCE") "10%"))
      (libsource (lib "DACֹֹ_Sources") (part "b4654b650e69147ec39a6b967a45e02"))
    )
    (comp (ref "C131")
      (value "CL31B475KPHNNNE")
      (footprint "C1206")
      (description "Cap Ceramic 4.7uF 10V X7R ±10% SMD 1206 +125°C Embossed T/R")
      (fields (field (name "TOLERANCE") "10%") (field (name "VOLTAGE") "10V"))
      (libsource (lib "DACֹֹ_Sources") (part "b4654b650e69147ec39a6b967a45e02"))
    )
    (comp (ref "C132")
      (value "CL31B475KPHNNNE")
      (footprint "C1206")
      (description "Cap Ceramic 4.7uF 10V X7R ±10% SMD 1206 +125°C Embossed T/R")
      (fields (field (name "TOLERANCE") "10%") (field (name "VOLTAGE") "10V"))
      (libsource (lib "DACֹֹ_Sources") (part "b4654b650e69147ec39a6b967a45e02"))
    )
    (comp (ref "C133")
      (value "C1005X7R1C104K050BC")
      (footprint "C0402")
      (description "Multilayer Ceramic Capacitors 100nF ±10% 16V X7R SMD 0402")
      (fields (field (name "VOLTAGE") "16V") (field (name "TOLERANCE") "10%"))
      (libsource (lib "DACֹֹ_Sources") (part "b4654b650e69147ec39a6b967a45e02"))
    )
    (comp (ref "C134")
      (value "C1005X7R1C104K050BC")
      (footprint "C0402")
      (description "Multilayer Ceramic Capacitors 100nF ±10% 16V X7R SMD 0402")
      (fields (field (name "VOLTAGE") "16V") (field (name "TOLERANCE") "10%"))
      (libsource (lib "DACֹֹ_Sources") (part "b4654b650e69147ec39a6b967a45e02"))
    )
    (comp (ref "C135")
      (value "C1005X7R1C104K050BC")
      (footprint "C0402")
      (description "Multilayer Ceramic Capacitors 100nF ±10% 16V X7R SMD 0402")
      (fields (field (name "VOLTAGE") "16V") (field (name "TOLERANCE") "10%"))
      (libsource (lib "DACֹֹ_Sources") (part "b4654b650e69147ec39a6b967a45e02"))
    )
    (comp (ref "C136")
      (value "C1005X7R1C104K050BC")
      (footprint "C0402")
      (description "Multilayer Ceramic Capacitors 100nF ±10% 16V X7R SMD 0402")
      (fields (field (name "VOLTAGE") "16V") (field (name "TOLERANCE") "10%"))
      (libsource (lib "DACֹֹ_Sources") (part "b4654b650e69147ec39a6b967a45e02"))
    )
    (comp (ref "C137")
      (value "C1005X7R1C104K050BC")
      (footprint "C0402")
      (description "Multilayer Ceramic Capacitors 100nF ±10% 16V X7R SMD 0402")
      (fields (field (name "VOLTAGE") "16V") (field (name "TOLERANCE") "10%"))
      (libsource (lib "DACֹֹ_Sources") (part "b4654b650e69147ec39a6b967a45e02"))
    )
    (comp (ref "C138")
      (value "C1005X7R1C104K050BC")
      (footprint "C0402")
      (description "Multilayer Ceramic Capacitors 100nF ±10% 16V X7R SMD 0402")
      (fields (field (name "VOLTAGE") "16V") (field (name "TOLERANCE") "10%"))
      (libsource (lib "DACֹֹ_Sources") (part "b4654b650e69147ec39a6b967a45e02"))
    )
    (comp (ref "C139")
      (value "C1005X7R1C104K050BC")
      (footprint "C0402")
      (description "Multilayer Ceramic Capacitors 100nF ±10% 16V X7R SMD 0402")
      (fields (field (name "VOLTAGE") "16V") (field (name "TOLERANCE") "10%"))
      (libsource (lib "DACֹֹ_Sources") (part "b4654b650e69147ec39a6b967a45e02"))
    )
    (comp (ref "C140")
      (value "C1005X7R1C104K050BC")
      (footprint "C0402")
      (description "Multilayer Ceramic Capacitors 100nF ±10% 16V X7R SMD 0402")
      (fields (field (name "VOLTAGE") "16V") (field (name "TOLERANCE") "10%"))
      (libsource (lib "DACֹֹ_Sources") (part "b4654b650e69147ec39a6b967a45e02"))
    )
    (comp (ref "C141")
      (value "C1005X7R1E103K050BB")
      (footprint "C0402")
      (description "Multilayer Ceramic Capacitors 10nF ±10% 25V X7R SMD 0402")
      (fields (field (name "TOLERANCE") "10%") (field (name "VOLTAGE") "25V"))
      (libsource (lib "DACֹֹ_Sources") (part "b4654b650e69147ec39a6b967a45e02"))
    )
    (comp (ref "C266")
      (value "CL31B475KPHNNNE")
      (footprint "C1206")
      (description "Cap Ceramic 4.7uF 10V X7R ±10% SMD 1206 +125°C Embossed T/R")
      (fields (field (name "TOLERANCE") "10%") (field (name "VOLTAGE") "10V"))
      (libsource (lib "DACֹֹ_Sources") (part "b4654b650e69147ec39a6b967a45e02"))
    )
    (comp (ref "C281")
      (value "C1005X7R1E103K050BB")
      (footprint "C0402")
      (description "Multilayer Ceramic Capacitors 10nF ±10% 25V X7R SMD 0402")
      (fields (field (name "TOLERANCE") "10%") (field (name "VOLTAGE") "25V"))
      (libsource (lib "DACֹֹ_Sources") (part "b4654b650e69147ec39a6b967a45e02"))
    )
    (comp (ref "C282")
      (value "C1005X7R1E103K050BB")
      (footprint "C0402")
      (description "Multilayer Ceramic Capacitors 10nF ±10% 25V X7R SMD 0402")
      (fields (field (name "TOLERANCE") "10%") (field (name "VOLTAGE") "25V"))
      (libsource (lib "DACֹֹ_Sources") (part "b4654b650e69147ec39a6b967a45e02"))
    )
    (comp (ref "C289")
      (value "C1608X7R1C105K080AC")
      (footprint "C0603")
      (description "Multilayer Ceramic Capacitors 1μF ±10% 16V X7R SMD 0603")
      (fields (field (name "VOLTAGE") "16V") (field (name "TOLERANCE") "10%"))
      (libsource (lib "DACֹֹ_Sources") (part "236180d848d6139a670b325ea6854c9"))
    )
    (comp (ref "C290")
      (value "C1005X7R1E103K050BB")
      (footprint "C0402")
      (description "Multilayer Ceramic Capacitors 10nF ±10% 25V X7R SMD 0402")
      (fields (field (name "TOLERANCE") "10%") (field (name "VOLTAGE") "25V"))
      (libsource (lib "DACֹֹ_Sources") (part "b4654b650e69147ec39a6b967a45e02"))
    )
    (comp (ref "C291")
      (value "GRM21BR71A106KE51L")
      (footprint "C0805")
      (fields (field (name "MANUFACTURER") "Murata"))
      (libsource (lib "DACֹֹ_Sources") (part "CAP"))
    )
    (comp (ref "C292")
      (value "GRM21BR71A106KE51L")
      (footprint "C0805")
      (fields (field (name "MANUFACTURER") "Murata"))
      (libsource (lib "DACֹֹ_Sources") (part "CAP"))
    )
    (comp (ref "C293")
      (value "C1608X7R1C105K080AC")
      (footprint "C0603")
      (description "Multilayer Ceramic Capacitors 1μF ±10% 16V X7R SMD 0603")
      (fields (field (name "VOLTAGE") "16V") (field (name "TOLERANCE") "10%"))
      (libsource (lib "DACֹֹ_Sources") (part "236180d848d6139a670b325ea6854c9"))
    )
    (comp (ref "C294")
      (value "C1005X7R1C104K050BC")
      (footprint "C0402")
      (description "Multilayer Ceramic Capacitors 100nF ±10% 16V X7R SMD 0402")
      (fields (field (name "VOLTAGE") "16V") (field (name "TOLERANCE") "10%"))
      (libsource (lib "DACֹֹ_Sources") (part "b4654b650e69147ec39a6b967a45e02"))
    )
    (comp (ref "C295")
      (value "C0603C220J5GACTU")
      (footprint "C0603")
      (description "Cap Ceramic 22pF 50V C0G 5% SMD 0603 125°C Paper T/R")
      (fields (field (name "TOLERANCE") "0.05") (field (name "MANUFACTURER") "KEMET"))
      (libsource (lib "DACֹֹ_Sources") (part "b4654b650e69147ec39a6b967a45e02"))
    )
    (comp (ref "C296")
      (value "GRM21BR71A106KE51L")
      (footprint "C0805")
      (fields (field (name "MANUFACTURER") "Murata"))
      (libsource (lib "DACֹֹ_Sources") (part "CAP"))
    )
    (comp (ref "C297")
      (value "C1608X7R1C105K080AC")
      (footprint "C0603")
      (description "Multilayer Ceramic Capacitors 1μF ±10% 16V X7R SMD 0603")
      (fields (field (name "VOLTAGE") "16V") (field (name "TOLERANCE") "10%"))
      (libsource (lib "DACֹֹ_Sources") (part "236180d848d6139a670b325ea6854c9"))
    )
    (comp (ref "C298")
      (value "C1005X7R1C104K050BC")
      (footprint "C0402")
      (description "Multilayer Ceramic Capacitors 100nF ±10% 16V X7R SMD 0402")
      (fields (field (name "VOLTAGE") "16V") (field (name "TOLERANCE") "10%"))
      (libsource (lib "DACֹֹ_Sources") (part "b4654b650e69147ec39a6b967a45e02"))
    )
    (comp (ref "C299")
      (value "GRM21BR71A106KE51L")
      (footprint "C0805")
      (fields (field (name "MANUFACTURER") "Murata"))
      (libsource (lib "DACֹֹ_Sources") (part "CAP"))
    )
    (comp (ref "C300")
      (value "C1608X7R1C105K080AC")
      (footprint "C0603")
      (description "Multilayer Ceramic Capacitors 1μF ±10% 16V X7R SMD 0603")
      (fields (field (name "VOLTAGE") "16V") (field (name "TOLERANCE") "10%"))
      (libsource (lib "DACֹֹ_Sources") (part "236180d848d6139a670b325ea6854c9"))
    )
    (comp (ref "C301")
      (value "C1005X7R1E103K050BB")
      (footprint "C0402")
      (description "Multilayer Ceramic Capacitors 10nF ±10% 25V X7R SMD 0402")
      (fields (field (name "TOLERANCE") "10%") (field (name "VOLTAGE") "25V"))
      (libsource (lib "DACֹֹ_Sources") (part "b4654b650e69147ec39a6b967a45e02"))
    )
    (comp (ref "C302")
      (value "GRM21BR71A106KE51L")
      (footprint "C0805")
      (fields (field (name "MANUFACTURER") "Murata"))
      (libsource (lib "DACֹֹ_Sources") (part "CAP"))
    )
    (comp (ref "C303")
      (value "GRM21BR71A106KE51L")
      (footprint "C0805")
      (fields (field (name "MANUFACTURER") "Murata"))
      (libsource (lib "DACֹֹ_Sources") (part "CAP"))
    )
    (comp (ref "C304")
      (value "C1608X7R1C105K080AC")
      (footprint "C0603")
      (description "Multilayer Ceramic Capacitors 1μF ±10% 16V X7R SMD 0603")
      (fields (field (name "VOLTAGE") "16V") (field (name "TOLERANCE") "10%"))
      (libsource (lib "DACֹֹ_Sources") (part "236180d848d6139a670b325ea6854c9"))
    )
    (comp (ref "C305")
      (value "C1005X7R1C104K050BC")
      (footprint "C0402")
      (description "Multilayer Ceramic Capacitors 100nF ±10% 16V X7R SMD 0402")
      (fields (field (name "VOLTAGE") "16V") (field (name "TOLERANCE") "10%"))
      (libsource (lib "DACֹֹ_Sources") (part "b4654b650e69147ec39a6b967a45e02"))
    )
    (comp (ref "D2")
      (value "LTST-C170TBKT")
      (footprint "FP-LTST-C170TBKT-MFG")
      (description "LED BLUE CLEAR SMD")
      (libsource (lib "DACֹֹ_Sources") (part "8706943c75ba83719d021d2fdc84c58"))
    )
    (comp (ref "FB7")
      (value "FBMJ3216HM600-T")
      (footprint "BEADC3216X130N")
      (description "Ind Chip Bead 60Ohm 25% Ferrite 4A 1206 T/R")
      (libsource (lib "DACֹֹ_Sources") (part "FBMJ3216HM600-T"))
    )
    (comp (ref "FB8")
      (value "NFM31PC276B0J3L")
      (footprint "FP-NFM31-0_2-MFG")
      (fields (field (name "VOLTAGE") "6.3V") (field (name "TOLERANCE") "20%"))
      (libsource (lib "DACֹֹ_Sources") (part "968ca41a07abfef6fd4f7114a56c54f"))
    )
    (comp (ref "FB9")
      (value "NFM31PC276B0J3L")
      (footprint "FP-NFM31-0_2-MFG")
      (fields (field (name "VOLTAGE") "6.3V") (field (name "TOLERANCE") "20%"))
      (libsource (lib "DACֹֹ_Sources") (part "968ca41a07abfef6fd4f7114a56c54f"))
    )
    (comp (ref "FB10")
      (value "BLM41PG102SN1L")
      (footprint "BLM41")
      (description "Ferrite Bead, 1806, 1000Ω @ 100MHz, 25%, 0.09Ω, 1.5A")
      (fields (field (name "TOLERANCE") "25%"))
      (libsource (lib "DACֹֹ_Sources") (part "5f30dd21d616792df468990f7003faa"))
    )
    (comp (ref "FB12")
      (value "BLM41PG102SN1L")
      (footprint "BLM41")
      (description "Ferrite Bead, 1806, 1000Ω @ 100MHz, 25%, 0.09Ω, 1.5A")
      (fields (field (name "TOLERANCE") "25%"))
      (libsource (lib "DACֹֹ_Sources") (part "5f30dd21d616792df468990f7003faa"))
    )
    (comp (ref "FB13")
      (value "BLM41PG102SN1L")
      (footprint "BLM41")
      (description "Ferrite Bead, 1806, 1000Ω @ 100MHz, 25%, 0.09Ω, 1.5A")
      (fields (field (name "TOLERANCE") "25%"))
      (libsource (lib "DACֹֹ_Sources") (part "5f30dd21d616792df468990f7003faa"))
    )
    (comp (ref "FB14")
      (value "NFM31PC276B0J3L")
      (footprint "FP-NFM31-0_2-MFG")
      (fields (field (name "VOLTAGE") "6.3V") (field (name "TOLERANCE") "20%"))
      (libsource (lib "DACֹֹ_Sources") (part "968ca41a07abfef6fd4f7114a56c54f"))
    )
    (comp (ref "FB15")
      (value "BLM41PG102SN1L")
      (footprint "BLM41")
      (description "Ferrite Bead, 1806, 1000Ω @ 100MHz, 25%, 0.09Ω, 1.5A")
      (fields (field (name "TOLERANCE") "25%"))
      (libsource (lib "DACֹֹ_Sources") (part "5f30dd21d616792df468990f7003faa"))
    )
    (comp (ref "FB16")
      (value "BLM41PG102SN1L")
      (footprint "BLM41")
      (description "Ferrite Bead, 1806, 1000Ω @ 100MHz, 25%, 0.09Ω, 1.5A")
      (fields (field (name "TOLERANCE") "25%"))
      (libsource (lib "DACֹֹ_Sources") (part "5f30dd21d616792df468990f7003faa"))
    )
    (comp (ref "FB24")
      (value "NFM31PC276B0J3L")
      (footprint "FP-NFM31-0_2-MFG")
      (fields (field (name "VOLTAGE") "6.3V") (field (name "TOLERANCE") "20%"))
      (libsource (lib "DACֹֹ_Sources") (part "968ca41a07abfef6fd4f7114a56c54f"))
    )
    (comp (ref "J6")
      (value "RAPC722X")
      (footprint "SWITCH-RAPC712X-3_V")
      (description "Power Jack, 5 A, 3-Pin THD, RoHS, Bulk")
      (fields (field (name "MANUFACTURER") "Switchcraft"))
      (libsource (lib "DACֹֹ_Sources") (part "SWITCH-RAPC712X-3"))
    )
    (comp (ref "L1")
      (value "LPS3015-222MR")
      (footprint "lps3015")
      (libsource (lib "DACֹֹ_Sources") (part "Component_1"))
    )
    (comp (ref "L2")
      (value "LPS3015-222MR")
      (footprint "lps3015")
      (libsource (lib "DACֹֹ_Sources") (part "Component_1"))
    )
    (comp (ref "L3")
      (value "LPS3015-222MR")
      (footprint "lps3015")
      (libsource (lib "DACֹֹ_Sources") (part "Component_1"))
    )
    (comp (ref "L4")
      (value "LPS3015-222MR")
      (footprint "lps3015")
      (libsource (lib "DACֹֹ_Sources") (part "Component_1"))
    )
    (comp (ref "L5")
      (value "LPS3015-222MR")
      (footprint "lps3015")
      (libsource (lib "DACֹֹ_Sources") (part "Component_1"))
    )
    (comp (ref "L70")
      (value "LPS3015-222MR")
      (footprint "lps3015")
      (libsource (lib "DACֹֹ_Sources") (part "Component_1"))
    )
    (comp (ref "Q1")
      (value "CSD18532Q5BT")
      (footprint "FP-DNK0008A-MFG")
      (description "MOSFET N-CH 60V 100A 8VSON")
      (libsource (lib "DACֹֹ_Sources") (part "7382af88e928fdc71488234cfaaf11c"))
    )
    (comp (ref "R32")
      (value "750K 5% 0402(1005)")
      (footprint "R0402")
      (description "750K 0.063W 5% 0402 (1005 Metric)  SMD")
      (fields (field (name "TOLERANCE") "5 %") (field (name "POWER") "0.063 W"))
      (libsource (lib "DACֹֹ_Sources") (part "RES"))
    )
    (comp (ref "R33")
      (value "ERJ-3EKF3092V")
      (footprint "R0603")
      (fields (field (name "MANUFACTURER") "Panasonic"))
      (libsource (lib "DACֹֹ_Sources") (part "RES"))
    )
    (comp (ref "R34")
      (value "ERJ3EKF1002V")
      (footprint "R0603")
      (description "Chip Resistor, 10 KOhm, +/- 1%, 0.1 W, -55 to 155 degC, 0603 (1608 Metric), RoHS, Tape and Reel")
      (fields (field (name "TOLERANCE") "1%") (field (name "MANUFACTURER") "Panasonic"))
      (libsource (lib "DACֹֹ_Sources") (part "RES-2"))
    )
    (comp (ref "R35")
      (value "ERJ3EKF1002V")
      (footprint "R0603")
      (description "Chip Resistor, 10 KOhm, +/- 1%, 0.1 W, -55 to 155 degC, 0603 (1608 Metric), RoHS, Tape and Reel")
      (fields (field (name "TOLERANCE") "1%") (field (name "MANUFACTURER") "Panasonic"))
      (libsource (lib "DACֹֹ_Sources") (part "RES-2"))
    )
    (comp (ref "R36")
      (value "RC0402FR-07150KL")
      (footprint "R0402")
      (description "RES 150K OHM 1% 1/16W 0402")
      (fields (field (name "TOLERANCE") "1%"))
      (libsource (lib "DACֹֹ_Sources") (part "1029c3af85768c4190bb7ad29bc67b5"))
    )
    (comp (ref "R37")
      (value "CRCW0603750KFKEA")
      (footprint "R0603")
      (fields (field (name "MANUFACTURER") "Vishay Dale"))
      (libsource (lib "DACֹֹ_Sources") (part "RES"))
    )
    (comp (ref "R38")
      (value "RC0603FR-07150KL")
      (footprint "R0603")
      (fields (field (name "TOLERANCE") "1%"))
      (libsource (lib "DACֹֹ_Sources") (part "1029c3af85768c4190bb7ad29bc67b5"))
    )
    (comp (ref "R39")
      (value "CRCW0603191KFKEA")
      (footprint "R0603")
      (fields (field (name "MANUFACTURER") "Vishay Dale"))
      (libsource (lib "DACֹֹ_Sources") (part "RES"))
    )
    (comp (ref "R40")
      (value "ERJ-2RKF1743X")
      (footprint "R0402")
      (fields (field (name "MANUFACTURER") "Panasonic"))
      (libsource (lib "DACֹֹ_Sources") (part "RES"))
    )
    (comp (ref "R41")
      (value "ERJ-3EKF1823V")
      (footprint "R0603")
      (fields (field (name "MANUFACTURER") "Panasonic"))
      (libsource (lib "DACֹֹ_Sources") (part "RES"))
    )
    (comp (ref "R42")
      (value "ERJ2RKF3303X")
      (footprint "R0402")
      (fields (field (name "MANUFACTURER") "Panasonic"))
      (libsource (lib "DACֹֹ_Sources") (part "RES"))
    )
    (comp (ref "R43")
      (value "ERJ-2RKF1743X")
      (footprint "R0402")
      (fields (field (name "MANUFACTURER") "Panasonic"))
      (libsource (lib "DACֹֹ_Sources") (part "RES"))
    )
    (comp (ref "R44")
      (value "ERJ2RKF3303X")
      (footprint "R0402")
      (fields (field (name "MANUFACTURER") "Panasonic"))
      (libsource (lib "DACֹֹ_Sources") (part "RES"))
    )
    (comp (ref "R51")
      (value "CRCW0603750KFKEA")
      (footprint "R0603")
      (fields (field (name "MANUFACTURER") "Vishay Dale"))
      (libsource (lib "DACֹֹ_Sources") (part "RES"))
    )
    (comp (ref "R52")
      (value "RC0603FR-07150KL")
      (footprint "R0603")
      (fields (field (name "TOLERANCE") "1%"))
      (libsource (lib "DACֹֹ_Sources") (part "1029c3af85768c4190bb7ad29bc67b5"))
    )
    (comp (ref "R53")
      (value "CRCW0603191KFKEA")
      (footprint "R0603")
      (fields (field (name "MANUFACTURER") "Vishay Dale"))
      (libsource (lib "DACֹֹ_Sources") (part "RES"))
    )
    (comp (ref "R54")
      (value "ERJ-2RKF1743X")
      (footprint "R0402")
      (fields (field (name "MANUFACTURER") "Panasonic"))
      (libsource (lib "DACֹֹ_Sources") (part "RES"))
    )
    (comp (ref "R55")
      (value "ERJ-3EKF1823V")
      (footprint "R0603")
      (fields (field (name "MANUFACTURER") "Panasonic"))
      (libsource (lib "DACֹֹ_Sources") (part "RES"))
    )
    (comp (ref "R56")
      (value "ERJ2RKF3303X")
      (footprint "R0402")
      (fields (field (name "MANUFACTURER") "Panasonic"))
      (libsource (lib "DACֹֹ_Sources") (part "RES"))
    )
    (comp (ref "R57")
      (value "ERJ-2RKF1743X")
      (footprint "R0402")
      (fields (field (name "MANUFACTURER") "Panasonic"))
      (libsource (lib "DACֹֹ_Sources") (part "RES"))
    )
    (comp (ref "R58")
      (value "ERJ2RKF3303X")
      (footprint "R0402")
      (fields (field (name "MANUFACTURER") "Panasonic"))
      (libsource (lib "DACֹֹ_Sources") (part "RES"))
    )
    (comp (ref "R82")
      (value "ERJ2GE0R00X")
      (footprint "R0402")
      (description "Chip Resistor, 0 Ohm, 0.1 W, -55 to 155 degC, 0402 (1005 Metric), RoHS, Tape and Reel")
      (fields (field (name "MANUFACTURER") "Panasonic") (field (name "TOLERANCE") "5%"))
      (libsource (lib "DACֹֹ_Sources") (part "RES-2"))
    )
    (comp (ref "R105")
      (value "ERJ-3EKF3092V")
      (footprint "R0603")
      (fields (field (name "MANUFACTURER") "Panasonic"))
      (libsource (lib "DACֹֹ_Sources") (part "RES"))
    )
    (comp (ref "R106")
      (value "ERJ3EKF1002V")
      (footprint "R0603")
      (description "Chip Resistor, 10 KOhm, +/- 1%, 0.1 W, -55 to 155 degC, 0603 (1608 Metric), RoHS, Tape and Reel")
      (fields (field (name "TOLERANCE") "1%") (field (name "MANUFACTURER") "Panasonic"))
      (libsource (lib "DACֹֹ_Sources") (part "RES-2"))
    )
    (comp (ref "R107")
      (value "750K 5% 0402(1005)")
      (footprint "R0402")
      (description "750K 0.063W 5% 0402 (1005 Metric)  SMD")
      (fields (field (name "TOLERANCE") "5 %") (field (name "POWER") "0.063 W"))
      (libsource (lib "DACֹֹ_Sources") (part "RES"))
    )
    (comp (ref "R108")
      (value "RC0402FR-07150KL")
      (footprint "R0402")
      (description "RES 150K OHM 1% 1/16W 0402")
      (fields (field (name "TOLERANCE") "1%"))
      (libsource (lib "DACֹֹ_Sources") (part "1029c3af85768c4190bb7ad29bc67b5"))
    )
    (comp (ref "R109")
      (value "ERJ-3EKF3092V")
      (footprint "R0603")
      (fields (field (name "MANUFACTURER") "Panasonic"))
      (libsource (lib "DACֹֹ_Sources") (part "RES"))
    )
    (comp (ref "R110")
      (value "ERJ3EKF1002V")
      (footprint "R0603")
      (description "Chip Resistor, 10 KOhm, +/- 1%, 0.1 W, -55 to 155 degC, 0603 (1608 Metric), RoHS, Tape and Reel")
      (fields (field (name "TOLERANCE") "1%") (field (name "MANUFACTURER") "Panasonic"))
      (libsource (lib "DACֹֹ_Sources") (part "RES-2"))
    )
    (comp (ref "U8")
      (value "TPS62290DRVR")
      (footprint "FP-DRV0006A-IPC_A")
      (description "IC REG BUCK ADJUSTABLE 1A 6SON")
      (libsource (lib "DACֹֹ_Sources") (part "e18bba32e79127f802312c6d0d2e879"))
    )
    (comp (ref "U9")
      (value "TPS7A8001DRBR")
      (footprint "DRB0008A_V")
      (fields (field (name "MANUFACTURER") "Texas Instruments"))
      (libsource (lib "DACֹֹ_Sources") (part "TI-TPS7A8X01DRB8-1750X1500TP"))
    )
    (comp (ref "U10")
      (value "TPS79633QDCQRQ1")
      (footprint "DCQ0006A")
      (fields (field (name "MANUFACTURER") "Texas Instruments") (field (name "PARTNUMBER") "TPS79633DCQ"))
      (libsource (lib "DACֹֹ_Sources") (part "TI-TPS7XXXXXXXX"))
    )
    (comp (ref "U11")
      (value "TPS62420DRCR")
      (footprint "DRC0010G")
      (fields (field (name "MANUFACTURER") "Texas Instruments"))
      (libsource (lib "DACֹֹ_Sources") (part "TI-TPS62420DRC10-2400X1650TP"))
    )
    (comp (ref "U12")
      (value "TPS71701DCKR")
      (footprint "DCK")
      (fields (field (name "MANUFACTURER") "Texas Instruments"))
      (libsource (lib "DACֹֹ_Sources") (part "TI-TPS7XX01-5"))
    )
    (comp (ref "U13")
      (value "TPS71701DCKR")
      (footprint "DCK")
      (fields (field (name "MANUFACTURER") "Texas Instruments"))
      (libsource (lib "DACֹֹ_Sources") (part "TI-TPS7XX01-5"))
    )
    (comp (ref "U14")
      (value "TPS2400DBVT")
      (footprint "DBV0005A")
      (description "5.5-V over voltage protection controller with 100-V input transient protection 5-SOT-23 -40 to 85")
      (fields
        (field (name "MF") "Texas Instruments")
        (field (name "BUYPART") "https://www.snapeda.com/parts/TPS2400DBVT/Texas%20Instruments/view-part/425327/?ref=eda")
      )
      (libsource (lib "DACֹֹ_Sources") (part "TPS2400DBVT"))
    )
    (comp (ref "U15")
      (value "TPS79633QDCQRQ1")
      (footprint "DCQ0006A")
      (fields (field (name "MANUFACTURER") "Texas Instruments") (field (name "PARTNUMBER") "TPS79633DCQ"))
      (libsource (lib "DACֹֹ_Sources") (part "TI-TPS7XXXXXXXX"))
    )
    (comp (ref "U16")
      (value "TPS62420DRCR")
      (footprint "DRC0010G")
      (fields (field (name "MANUFACTURER") "Texas Instruments"))
      (libsource (lib "DACֹֹ_Sources") (part "TI-TPS62420DRC10-2400X1650TP"))
    )
    (comp (ref "U17")
      (value "TPS71701DCKR")
      (footprint "DCK")
      (fields (field (name "MANUFACTURER") "Texas Instruments"))
      (libsource (lib "DACֹֹ_Sources") (part "TI-TPS7XX01-5"))
    )
    (comp (ref "U18")
      (value "TPS71701DCKR")
      (footprint "DCK")
      (fields (field (name "MANUFACTURER") "Texas Instruments"))
      (libsource (lib "DACֹֹ_Sources") (part "TI-TPS7XX01-5"))
    )
    (comp (ref "U19")
      (value "ADP1706ARDZ-3.3-R7")
      (footprint "ADI-RD-8-2_M")
      (fields (field (name "MANUFACTURER") "Analog Devices"))
      (libsource (lib "DACֹֹ_Sources") (part "ADI-ADP1706-RD-8-2"))
    )
    (comp (ref "U20")
      (value "ADP1706ARDZ-1.8-R7")
      (footprint "ADI-RD-8-2_M")
      (fields (field (name "MANUFACTURER") "Analog Devices"))
      (libsource (lib "DACֹֹ_Sources") (part "ADI-ADP1706-RD-8-2"))
    )
    (comp (ref "U21")
      (value "ADP1706ARDZ-1.8-R7")
      (footprint "ADI-RD-8-2_M")
      (fields (field (name "MANUFACTURER") "Analog Devices"))
      (libsource (lib "DACֹֹ_Sources") (part "ADI-ADP1706-RD-8-2"))
    )
    (comp (ref "U31")
      (value "TPS7A8001DRBR")
      (footprint "DRB0008A_V")
      (fields (field (name "MANUFACTURER") "Texas Instruments"))
      (libsource (lib "DACֹֹ_Sources") (part "TI-TPS7A8X01DRB8-1750X1500TP"))
    )
    (comp (ref "U32")
      (value "TPS62290DRVR")
      (footprint "FP-DRV0006A-IPC_A")
      (description "IC REG BUCK ADJUSTABLE 1A 6SON")
      (libsource (lib "DACֹֹ_Sources") (part "e18bba32e79127f802312c6d0d2e879"))
    )
    (comp (ref "U33")
      (value "TPS7A8001DRBR")
      (footprint "DRB0008A_V")
      (fields (field (name "MANUFACTURER") "Texas Instruments"))
      (libsource (lib "DACֹֹ_Sources") (part "TI-TPS7A8X01DRB8-1750X1500TP"))
    )
  )
  (nets
    (net (code "1") (name "/1.2VCLK_DAC1") (class "Default")
      (node (ref "C73") (pin "2") (pinfunction "2_2") (pintype "passive"))
      (node (ref "C74") (pin "1") (pinfunction "1_1") (pintype "passive"))
      (node (ref "C76") (pin "2") (pinfunction "2_2") (pintype "passive"))
      (node (ref "FB13") (pin "2") (pinfunction "2_2") (pintype "passive"))
    )
    (net (code "2") (name "/1.2VCLK_DAC2") (class "Default")
      (node (ref "C108") (pin "2") (pinfunction "2_2") (pintype "passive"))
      (node (ref "C109") (pin "1") (pinfunction "1_1") (pintype "passive"))
      (node (ref "C111") (pin "2") (pinfunction "2_2") (pintype "passive"))
      (node (ref "FB16") (pin "2") (pinfunction "2_2") (pintype "passive"))
    )
    (net (code "3") (name "/1.2VDAC1") (class "Default")
      (node (ref "C66") (pin "2") (pinfunction "2_2") (pintype "passive"))
      (node (ref "C67") (pin "1") (pinfunction "1_1") (pintype "passive"))
      (node (ref "C69") (pin "2") (pinfunction "2_2") (pintype "passive"))
      (node (ref "FB10") (pin "2") (pinfunction "2_2") (pintype "passive"))
    )
    (net (code "4") (name "/1.2VDAC2") (class "Default")
      (node (ref "C101") (pin "2") (pinfunction "2_2") (pintype "passive"))
      (node (ref "C102") (pin "1") (pinfunction "1_1") (pintype "passive"))
      (node (ref "C104") (pin "2") (pinfunction "2_2") (pintype "passive"))
      (node (ref "FB15") (pin "2") (pinfunction "2_2") (pintype "passive"))
    )
    (net (code "5") (name "/1.2VDIGI_DAC1") (class "Default")
      (node (ref "C62") (pin "1") (pinfunction "1_1") (pintype "passive"))
      (node (ref "C63") (pin "2") (pinfunction "2_2") (pintype "passive"))
      (node (ref "C70") (pin "1") (pinfunction "1_1") (pintype "passive"))
      (node (ref "C77") (pin "1") (pinfunction "1_1") (pintype "passive"))
      (node (ref "FB9") (pin "3") (pinfunction "Output_3") (pintype "passive"))
      (node (ref "U12") (pin "1") (pinfunction "IN_1") (pintype "power_in"))
      (node (ref "U12") (pin "3") (pinfunction "EN_3") (pintype "input"))
      (node (ref "U13") (pin "1") (pinfunction "IN_1") (pintype "power_in"))
      (node (ref "U13") (pin "3") (pinfunction "EN_3") (pintype "input"))
    )
    (net (code "6") (name "/1.2VDIGI_DAC2") (class "Default")
      (node (ref "C105") (pin "1") (pinfunction "1_1") (pintype "passive"))
      (node (ref "C112") (pin "1") (pinfunction "1_1") (pintype "passive"))
      (node (ref "C97") (pin "1") (pinfunction "1_1") (pintype "passive"))
      (node (ref "C98") (pin "2") (pinfunction "2_2") (pintype "passive"))
      (node (ref "FB14") (pin "3") (pinfunction "Output_3") (pintype "passive"))
      (node (ref "U17") (pin "1") (pinfunction "IN_1") (pintype "power_in"))
      (node (ref "U17") (pin "3") (pinfunction "EN_3") (pintype "input"))
      (node (ref "U18") (pin "1") (pinfunction "IN_1") (pintype "power_in"))
      (node (ref "U18") (pin "3") (pinfunction "EN_3") (pintype "input"))
    )
    (net (code "7") (name "/1.8V_AVDD") (class "Default")
      (node (ref "C116") (pin "1") (pinfunction "1_1") (pintype "passive"))
      (node (ref "C117") (pin "1") (pinfunction "1_1") (pintype "passive"))
      (node (ref "C118") (pin "1") (pinfunction "1_1") (pintype "passive"))
      (node (ref "C119") (pin "1") (pinfunction "1_1") (pintype "passive"))
      (node (ref "C120") (pin "1") (pinfunction "1_1") (pintype "passive"))
      (node (ref "C122") (pin "1") (pinfunction "1_1") (pintype "passive"))
      (node (ref "C124") (pin "1") (pinfunction "1_1") (pintype "passive"))
      (node (ref "C125") (pin "1") (pinfunction "1_1") (pintype "passive"))
      (node (ref "C126") (pin "1") (pinfunction "1_1") (pintype "passive"))
      (node (ref "C127") (pin "1") (pinfunction "1_1") (pintype "passive"))
      (node (ref "C128") (pin "1") (pinfunction "1_1") (pintype "passive"))
      (node (ref "C129") (pin "1") (pinfunction "1_1") (pintype "passive"))
      (node (ref "C130") (pin "1") (pinfunction "1_1") (pintype "passive"))
      (node (ref "U20") (pin "5") (pinfunction "OUT_5") (pintype "power_in"))
      (node (ref "U20") (pin "6") (pinfunction "OUT_6") (pintype "power_in"))
      (node (ref "U20") (pin "7") (pinfunction "SENSE_7") (pintype "input"))
    )
    (net (code "8") (name "/1.8V_DRVDD") (class "Default")
      (node (ref "C132") (pin "1") (pinfunction "1_1") (pintype "passive"))
      (node (ref "C133") (pin "1") (pinfunction "1_1") (pintype "passive"))
      (node (ref "C134") (pin "1") (pinfunction "1_1") (pintype "passive"))
      (node (ref "C135") (pin "1") (pinfunction "1_1") (pintype "passive"))
      (node (ref "U21") (pin "5") (pinfunction "OUT_5") (pintype "power_in"))
      (node (ref "U21") (pin "6") (pinfunction "OUT_6") (pintype "power_in"))
      (node (ref "U21") (pin "7") (pinfunction "SENSE_7") (pintype "input"))
    )
    (net (code "9") (name "/3.3VA_DAC1") (class "Default")
      (node (ref "C53") (pin "2") (pinfunction "2_2") (pintype "passive"))
      (node (ref "C54") (pin "1") (pinfunction "1_1") (pintype "passive"))
      (node (ref "C56") (pin "2") (pinfunction "2_2") (pintype "passive"))
      (node (ref "U10") (pin "4") (pinfunction "OUT_4") (pintype "power_in"))
    )
    (net (code "10") (name "/3.3VA_DAC2") (class "Default")
      (node (ref "C88") (pin "2") (pinfunction "2_2") (pintype "passive"))
      (node (ref "C89") (pin "1") (pinfunction "1_1") (pintype "passive"))
      (node (ref "C91") (pin "2") (pinfunction "2_2") (pintype "passive"))
      (node (ref "U15") (pin "4") (pinfunction "OUT_4") (pintype "power_in"))
    )
    (net (code "11") (name "/3.3VCLK") (class "Default")
      (node (ref "C35") (pin "2") (pinfunction "2_2") (pintype "passive"))
      (node (ref "C36") (pin "1") (pinfunction "1_1") (pintype "passive"))
      (node (ref "C38") (pin "2") (pinfunction "2_2") (pintype "passive"))
      (node (ref "FB12") (pin "1") (pinfunction "1_1") (pintype "passive"))
      (node (ref "R33") (pin "2") (pinfunction "2_2") (pintype "passive"))
      (node (ref "U9") (pin "1") (pinfunction "OUT_1") (pintype "power_in"))
      (node (ref "U9") (pin "2") (pinfunction "OUT_2") (pintype "power_in"))
    )
    (net (code "12") (name "/3.3V_AVDD") (class "Default")
      (node (ref "C114") (pin "1") (pinfunction "1_1") (pintype "passive"))
      (node (ref "C136") (pin "1") (pinfunction "1_1") (pintype "passive"))
      (node (ref "C137") (pin "1") (pinfunction "1_1") (pintype "passive"))
      (node (ref "C138") (pin "1") (pinfunction "1_1") (pintype "passive"))
      (node (ref "C139") (pin "1") (pinfunction "1_1") (pintype "passive"))
      (node (ref "C140") (pin "1") (pinfunction "1_1") (pintype "passive"))
      (node (ref "U19") (pin "5") (pinfunction "OUT_5") (pintype "power_in"))
      (node (ref "U19") (pin "6") (pinfunction "OUT_6") (pintype "power_in"))
      (node (ref "U19") (pin "7") (pinfunction "SENSE_7") (pintype "input"))
    )
    (net (code "13") (name "/3.3V_LOGIC") (class "Default")
      (node (ref "FB12") (pin "2") (pinfunction "2_2") (pintype "passive"))
    )
    (net (code "14") (name "/5V_AVDD") (class "Default")
      (node (ref "R82") (pin "2") (pinfunction "2_2") (pintype "passive"))
    )
    (net (code "15") (name "/6V") (class "Default")
      (node (ref "C113") (pin "1") (pinfunction "1_1") (pintype "passive"))
      (node (ref "C121") (pin "1") (pinfunction "1_1") (pintype "passive"))
      (node (ref "C131") (pin "1") (pinfunction "1_1") (pintype "passive"))
      (node (ref "C266") (pin "1") (pinfunction "1_1") (pintype "passive"))
      (node (ref "C296") (pin "2") (pinfunction "2_2") (pintype "passive"))
      (node (ref "C297") (pin "2") (pinfunction "2_2") (pintype "passive"))
      (node (ref "C298") (pin "1") (pinfunction "1_1") (pintype "passive"))
      (node (ref "C40") (pin "2") (pinfunction "2_2") (pintype "passive"))
      (node (ref "C42") (pin "2") (pinfunction "2_2") (pintype "passive"))
      (node (ref "C43") (pin "1") (pinfunction "1_1") (pintype "passive"))
      (node (ref "C45") (pin "2") (pinfunction "2_2") (pintype "passive"))
      (node (ref "C47") (pin "1") (pinfunction "1_1") (pintype "passive"))
      (node (ref "C48") (pin "1") (pinfunction "1_1") (pintype "passive"))
      (node (ref "C57") (pin "2") (pinfunction "2_2") (pintype "passive"))
      (node (ref "C58") (pin "2") (pinfunction "2_2") (pintype "passive"))
      (node (ref "C59") (pin "1") (pinfunction "1_1") (pintype "passive"))
      (node (ref "C60") (pin "1") (pinfunction "1_1") (pintype "passive"))
      (node (ref "C92") (pin "2") (pinfunction "2_2") (pintype "passive"))
      (node (ref "C93") (pin "2") (pinfunction "2_2") (pintype "passive"))
      (node (ref "C94") (pin "1") (pinfunction "1_1") (pintype "passive"))
      (node (ref "C95") (pin "1") (pinfunction "1_1") (pintype "passive"))
      (node (ref "FB7") (pin "2") (pinfunction "2_2") (pintype "passive"))
      (node (ref "R34") (pin "2") (pinfunction "2_2") (pintype "passive"))
      (node (ref "R82") (pin "1") (pinfunction "1_1") (pintype "passive"))
      (node (ref "U11") (pin "2") (pinfunction "MODE/DATA_2") (pintype "bidirectional"))
      (node (ref "U11") (pin "3") (pinfunction "VIN_3") (pintype "power_in"))
      (node (ref "U11") (pin "7") (pinfunction "EN1_7") (pintype "input"))
      (node (ref "U11") (pin "9") (pinfunction "EN2_9") (pintype "input"))
      (node (ref "U16") (pin "2") (pinfunction "MODE/DATA_2") (pintype "bidirectional"))
      (node (ref "U16") (pin "3") (pinfunction "VIN_3") (pintype "power_in"))
      (node (ref "U16") (pin "7") (pinfunction "EN1_7") (pintype "input"))
      (node (ref "U16") (pin "9") (pinfunction "EN2_9") (pintype "input"))
      (node (ref "U19") (pin "1") (pinfunction "EN_1") (pintype "input"))
      (node (ref "U19") (pin "3") (pinfunction "IN_3") (pintype "power_in"))
      (node (ref "U19") (pin "4") (pinfunction "IN_4") (pintype "power_in"))
      (node (ref "U20") (pin "1") (pinfunction "EN_1") (pintype "input"))
      (node (ref "U20") (pin "3") (pinfunction "IN_3") (pintype "power_in"))
      (node (ref "U20") (pin "4") (pinfunction "IN_4") (pintype "power_in"))
      (node (ref "U21") (pin "1") (pinfunction "EN_1") (pintype "input"))
      (node (ref "U21") (pin "3") (pinfunction "IN_3") (pintype "power_in"))
      (node (ref "U21") (pin "4") (pinfunction "IN_4") (pintype "power_in"))
      (node (ref "U32") (pin "4") (pinfunction "EN_4") (pintype "input"))
      (node (ref "U32") (pin "5") (pinfunction "VIN_5") (pintype "power_in"))
      (node (ref "U8") (pin "4") (pinfunction "EN_4") (pintype "input"))
      (node (ref "U8") (pin "5") (pinfunction "VIN_5") (pintype "power_in"))
    )
    (net (code "16") (name "/6V_IN") (class "Default")
      (node (ref "J6") (pin "1") (pinfunction "1_1") (pintype "passive"))
      (node (ref "Q1") (pin "5-6-7-8") (pinfunction "D_5-6-7-8") (pintype "passive"))
      (node (ref "U14") (pin "5") (pinfunction "VIN_5") (pintype "input"))
    )
    (net (code "17") (name "/DEF1") (class "Default")
      (node (ref "R37") (pin "1") (pinfunction "1_1") (pintype "passive"))
      (node (ref "R38") (pin "2") (pinfunction "2_2") (pintype "passive"))
      (node (ref "U11") (pin "5") (pinfunction "DEF_1_5") (pintype "input"))
    )
    (net (code "18") (name "/DEF2") (class "Default")
      (node (ref "R51") (pin "1") (pinfunction "1_1") (pintype "passive"))
      (node (ref "R52") (pin "2") (pinfunction "2_2") (pintype "passive"))
      (node (ref "U16") (pin "5") (pinfunction "DEF_1_5") (pintype "input"))
    )
    (net (code "19") (name "/VCCO_34") (class "Default")
      (node (ref "C289") (pin "2") (pinfunction "2_2") (pintype "passive"))
      (node (ref "C290") (pin "1") (pinfunction "1_1") (pintype "passive"))
      (node (ref "C292") (pin "2") (pinfunction "2_2") (pintype "passive"))
      (node (ref "C300") (pin "2") (pinfunction "2_2") (pintype "passive"))
      (node (ref "C301") (pin "1") (pinfunction "1_1") (pintype "passive"))
      (node (ref "C303") (pin "2") (pinfunction "2_2") (pintype "passive"))
      (node (ref "R105") (pin "2") (pinfunction "2_2") (pintype "passive"))
      (node (ref "R109") (pin "2") (pinfunction "2_2") (pintype "passive"))
      (node (ref "U31") (pin "1") (pinfunction "OUT_1") (pintype "power_in"))
      (node (ref "U31") (pin "2") (pinfunction "OUT_2") (pintype "power_in"))
      (node (ref "U33") (pin "1") (pinfunction "OUT_1") (pintype "power_in"))
      (node (ref "U33") (pin "2") (pinfunction "OUT_2") (pintype "power_in"))
    )
    (net (code "20") (name "/VIN_HDR") (class "Default")
      (node (ref "C41") (pin "1") (pinfunction "1_1") (pintype "passive"))
      (node (ref "C49") (pin "1") (pinfunction "1_1") (pintype "passive"))
      (node (ref "FB7") (pin "1") (pinfunction "1_1") (pintype "passive"))
      (node (ref "Q1") (pin "1") (pinfunction "S_1") (pintype "passive"))
      (node (ref "Q1") (pin "2") (pinfunction "S_2") (pintype "passive"))
      (node (ref "Q1") (pin "3") (pinfunction "S_3") (pintype "passive"))
    )
    (net (code "21") (name "GND") (class "Default")
      (node (ref "C100") (pin "2") (pinfunction "2_2") (pintype "passive"))
      (node (ref "C101") (pin "1") (pinfunction "1_1") (pintype "passive"))
      (node (ref "C102") (pin "2") (pinfunction "2_2") (pintype "passive"))
      (node (ref "C103") (pin "1") (pinfunction "1_1") (pintype "passive"))
      (node (ref "C104") (pin "1") (pinfunction "1_1") (pintype "passive"))
      (node (ref "C105") (pin "2") (pinfunction "2_2") (pintype "passive"))
      (node (ref "C106") (pin "1") (pinfunction "1_1") (pintype "passive"))
      (node (ref "C107") (pin "2") (pinfunction "2_2") (pintype "passive"))
      (node (ref "C108") (pin "1") (pinfunction "1_1") (pintype "passive"))
      (node (ref "C109") (pin "2") (pinfunction "2_2") (pintype "passive"))
      (node (ref "C110") (pin "1") (pinfunction "1_1") (pintype "passive"))
      (node (ref "C111") (pin "1") (pinfunction "1_1") (pintype "passive"))
      (node (ref "C112") (pin "2") (pinfunction "2_2") (pintype "passive"))
      (node (ref "C113") (pin "2") (pinfunction "2_2") (pintype "passive"))
      (node (ref "C114") (pin "2") (pinfunction "2_2") (pintype "passive"))
      (node (ref "C115") (pin "2") (pinfunction "2_2") (pintype "passive"))
      (node (ref "C116") (pin "2") (pinfunction "2_2") (pintype "passive"))
      (node (ref "C117") (pin "2") (pinfunction "2_2") (pintype "passive"))
      (node (ref "C118") (pin "2") (pinfunction "2_2") (pintype "passive"))
      (node (ref "C119") (pin "2") (pinfunction "2_2") (pintype "passive"))
      (node (ref "C120") (pin "2") (pinfunction "2_2") (pintype "passive"))
      (node (ref "C121") (pin "2") (pinfunction "2_2") (pintype "passive"))
      (node (ref "C122") (pin "2") (pinfunction "2_2") (pintype "passive"))
      (node (ref "C123") (pin "2") (pinfunction "2_2") (pintype "passive"))
      (node (ref "C124") (pin "2") (pinfunction "2_2") (pintype "passive"))
      (node (ref "C125") (pin "2") (pinfunction "2_2") (pintype "passive"))
      (node (ref "C126") (pin "2") (pinfunction "2_2") (pintype "passive"))
      (node (ref "C127") (pin "2") (pinfunction "2_2") (pintype "passive"))
      (node (ref "C128") (pin "2") (pinfunction "2_2") (pintype "passive"))
      (node (ref "C129") (pin "2") (pinfunction "2_2") (pintype "passive"))
      (node (ref "C130") (pin "2") (pinfunction "2_2") (pintype "passive"))
      (node (ref "C131") (pin "2") (pinfunction "2_2") (pintype "passive"))
      (node (ref "C132") (pin "2") (pinfunction "2_2") (pintype "passive"))
      (node (ref "C133") (pin "2") (pinfunction "2_2") (pintype "passive"))
      (node (ref "C134") (pin "2") (pinfunction "2_2") (pintype "passive"))
      (node (ref "C135") (pin "2") (pinfunction "2_2") (pintype "passive"))
      (node (ref "C136") (pin "2") (pinfunction "2_2") (pintype "passive"))
      (node (ref "C137") (pin "2") (pinfunction "2_2") (pintype "passive"))
      (node (ref "C138") (pin "2") (pinfunction "2_2") (pintype "passive"))
      (node (ref "C139") (pin "2") (pinfunction "2_2") (pintype "passive"))
      (node (ref "C140") (pin "2") (pinfunction "2_2") (pintype "passive"))
      (node (ref "C141") (pin "2") (pinfunction "2_2") (pintype "passive"))
      (node (ref "C266") (pin "2") (pinfunction "2_2") (pintype "passive"))
      (node (ref "C281") (pin "2") (pinfunction "2_2") (pintype "passive"))
      (node (ref "C282") (pin "2") (pinfunction "2_2") (pintype "passive"))
      (node (ref "C289") (pin "1") (pinfunction "1_1") (pintype "passive"))
      (node (ref "C290") (pin "2") (pinfunction "2_2") (pintype "passive"))
      (node (ref "C291") (pin "1") (pinfunction "1_1") (pintype "passive"))
      (node (ref "C292") (pin "1") (pinfunction "1_1") (pintype "passive"))
      (node (ref "C293") (pin "1") (pinfunction "1_1") (pintype "passive"))
      (node (ref "C294") (pin "2") (pinfunction "2_2") (pintype "passive"))
      (node (ref "C296") (pin "1") (pinfunction "1_1") (pintype "passive"))
      (node (ref "C297") (pin "1") (pinfunction "1_1") (pintype "passive"))
      (node (ref "C298") (pin "2") (pinfunction "2_2") (pintype "passive"))
      (node (ref "C299") (pin "1") (pinfunction "1_1") (pintype "passive"))
      (node (ref "C300") (pin "1") (pinfunction "1_1") (pintype "passive"))
      (node (ref "C301") (pin "2") (pinfunction "2_2") (pintype "passive"))
      (node (ref "C302") (pin "1") (pinfunction "1_1") (pintype "passive"))
      (node (ref "C303") (pin "1") (pinfunction "1_1") (pintype "passive"))
      (node (ref "C304") (pin "1") (pinfunction "1_1") (pintype "passive"))
      (node (ref "C305") (pin "2") (pinfunction "2_2") (pintype "passive"))
      (node (ref "C35") (pin "1") (pinfunction "1_1") (pintype "passive"))
      (node (ref "C36") (pin "2") (pinfunction "2_2") (pintype "passive"))
      (node (ref "C37") (pin "1") (pinfunction "1_1") (pintype "passive"))
      (node (ref "C38") (pin "1") (pinfunction "1_1") (pintype "passive"))
      (node (ref "C39") (pin "1") (pinfunction "1_1") (pintype "passive"))
      (node (ref "C40") (pin "1") (pinfunction "1_1") (pintype "passive"))
      (node (ref "C41") (pin "2") (pinfunction "2_2") (pintype "passive"))
      (node (ref "C42") (pin "1") (pinfunction "1_1") (pintype "passive"))
      (node (ref "C43") (pin "2") (pinfunction "2_2") (pintype "passive"))
      (node (ref "C44") (pin "2") (pinfunction "2_2") (pintype "passive"))
      (node (ref "C45") (pin "1") (pinfunction "1_1") (pintype "passive"))
      (node (ref "C46") (pin "1") (pinfunction "1_1") (pintype "passive"))
      (node (ref "C47") (pin "2") (pinfunction "2_2") (pintype "passive"))
      (node (ref "C48") (pin "2") (pinfunction "2_2") (pintype "passive"))
      (node (ref "C49") (pin "2") (pinfunction "2_2") (pintype "passive"))
      (node (ref "C50") (pin "2") (pinfunction "GND_2") (pintype "passive"))
      (node (ref "C51") (pin "2") (pinfunction "2_2") (pintype "passive"))
      (node (ref "C52") (pin "2") (pinfunction "2_2") (pintype "passive"))
      (node (ref "C53") (pin "1") (pinfunction "1_1") (pintype "passive"))
      (node (ref "C54") (pin "2") (pinfunction "2_2") (pintype "passive"))
      (node (ref "C55") (pin "1") (pinfunction "1_1") (pintype "passive"))
      (node (ref "C56") (pin "1") (pinfunction "1_1") (pintype "passive"))
      (node (ref "C57") (pin "1") (pinfunction "1_1") (pintype "passive"))
      (node (ref "C58") (pin "1") (pinfunction "1_1") (pintype "passive"))
      (node (ref "C59") (pin "2") (pinfunction "2_2") (pintype "passive"))
      (node (ref "C60") (pin "2") (pinfunction "2_2") (pintype "passive"))
      (node (ref "C61") (pin "2") (pinfunction "2_2") (pintype "passive"))
      (node (ref "C62") (pin "2") (pinfunction "2_2") (pintype "passive"))
      (node (ref "C63") (pin "1") (pinfunction "1_1") (pintype "passive"))
      (node (ref "C64") (pin "1") (pinfunction "1_1") (pintype "passive"))
      (node (ref "C65") (pin "2") (pinfunction "2_2") (pintype "passive"))
      (node (ref "C66") (pin "1") (pinfunction "1_1") (pintype "passive"))
      (node (ref "C67") (pin "2") (pinfunction "2_2") (pintype "passive"))
      (node (ref "C68") (pin "1") (pinfunction "1_1") (pintype "passive"))
      (node (ref "C69") (pin "1") (pinfunction "1_1") (pintype "passive"))
      (node (ref "C70") (pin "2") (pinfunction "2_2") (pintype "passive"))
      (node (ref "C71") (pin "1") (pinfunction "1_1") (pintype "passive"))
      (node (ref "C72") (pin "2") (pinfunction "2_2") (pintype "passive"))
      (node (ref "C73") (pin "1") (pinfunction "1_1") (pintype "passive"))
      (node (ref "C74") (pin "2") (pinfunction "2_2") (pintype "passive"))
      (node (ref "C75") (pin "1") (pinfunction "1_1") (pintype "passive"))
      (node (ref "C76") (pin "1") (pinfunction "1_1") (pintype "passive"))
      (node (ref "C77") (pin "2") (pinfunction "2_2") (pintype "passive"))
      (node (ref "C85") (pin "2") (pinfunction "GND_2") (pintype "passive"))
      (node (ref "C86") (pin "2") (pinfunction "2_2") (pintype "passive"))
      (node (ref "C87") (pin "2") (pinfunction "2_2") (pintype "passive"))
      (node (ref "C88") (pin "1") (pinfunction "1_1") (pintype "passive"))
      (node (ref "C89") (pin "2") (pinfunction "2_2") (pintype "passive"))
      (node (ref "C90") (pin "1") (pinfunction "1_1") (pintype "passive"))
      (node (ref "C91") (pin "1") (pinfunction "1_1") (pintype "passive"))
      (node (ref "C92") (pin "1") (pinfunction "1_1") (pintype "passive"))
      (node (ref "C93") (pin "1") (pinfunction "1_1") (pintype "passive"))
      (node (ref "C94") (pin "2") (pinfunction "2_2") (pintype "passive"))
      (node (ref "C95") (pin "2") (pinfunction "2_2") (pintype "passive"))
      (node (ref "C96") (pin "2") (pinfunction "2_2") (pintype "passive"))
      (node (ref "C97") (pin "2") (pinfunction "2_2") (pintype "passive"))
      (node (ref "C98") (pin "1") (pinfunction "1_1") (pintype "passive"))
      (node (ref "C99") (pin "1") (pinfunction "1_1") (pintype "passive"))
      (node (ref "D2") (pin "1") (pinfunction "C_1") (pintype "passive"))
      (node (ref "FB14") (pin "2") (pinfunction "GND_2") (pintype "passive"))
      (node (ref "FB24") (pin "2") (pinfunction "GND_2") (pintype "passive"))
      (node (ref "FB8") (pin "2") (pinfunction "GND_2") (pintype "passive"))
      (node (ref "FB9") (pin "2") (pinfunction "GND_2") (pintype "passive"))
      (node (ref "J6") (pin "2") (pinfunction "2_2") (pintype "passive"))
      (node (ref "J6") (pin "3") (pinfunction "3_3") (pintype "passive"))
      (node (ref "R106") (pin "1") (pinfunction "1_1") (pintype "passive"))
      (node (ref "R108") (pin "1") (pinfunction "1_1") (pintype "passive"))
      (node (ref "R110") (pin "1") (pinfunction "1_1") (pintype "passive"))
      (node (ref "R35") (pin "1") (pinfunction "1_1") (pintype "passive"))
      (node (ref "R36") (pin "1") (pinfunction "1_1") (pintype "passive"))
      (node (ref "R38") (pin "1") (pinfunction "1_1") (pintype "passive"))
      (node (ref "R41") (pin "1") (pinfunction "1_1") (pintype "passive"))
      (node (ref "R42") (pin "1") (pinfunction "1_1") (pintype "passive"))
      (node (ref "R44") (pin "1") (pinfunction "1_1") (pintype "passive"))
      (node (ref "R52") (pin "1") (pinfunction "1_1") (pintype "passive"))
      (node (ref "R55") (pin "1") (pinfunction "1_1") (pintype "passive"))
      (node (ref "R56") (pin "1") (pinfunction "1_1") (pintype "passive"))
      (node (ref "R58") (pin "1") (pinfunction "1_1") (pintype "passive"))
      (node (ref "U10") (pin "3") (pinfunction "GND_3") (pintype "power_in"))
      (node (ref "U10") (pin "6") (pinfunction "GND_6") (pintype "power_in"))
      (node (ref "U11") (pin "11") (pinfunction "PP_11") (pintype "power_in"))
      (node (ref "U11") (pin "8") (pinfunction "GND_8") (pintype "power_in"))
      (node (ref "U12") (pin "2") (pinfunction "GND_2") (pintype "power_in"))
      (node (ref "U13") (pin "2") (pinfunction "GND_2") (pintype "power_in"))
      (node (ref "U14") (pin "2") (pinfunction "GND_2") (pintype "power_in"))
      (node (ref "U15") (pin "3") (pinfunction "GND_3") (pintype "power_in"))
      (node (ref "U15") (pin "6") (pinfunction "GND_6") (pintype "power_in"))
      (node (ref "U16") (pin "11") (pinfunction "PP_11") (pintype "power_in"))
      (node (ref "U16") (pin "8") (pinfunction "GND_8") (pintype "power_in"))
      (node (ref "U17") (pin "2") (pinfunction "GND_2") (pintype "power_in"))
      (node (ref "U18") (pin "2") (pinfunction "GND_2") (pintype "power_in"))
      (node (ref "U19") (pin "2") (pinfunction "GND_2") (pintype "power_in"))
      (node (ref "U19") (pin "9") (pinfunction "EP_9") (pintype "power_in"))
      (node (ref "U20") (pin "2") (pinfunction "GND_2") (pintype "power_in"))
      (node (ref "U20") (pin "9") (pinfunction "EP_9") (pintype "power_in"))
      (node (ref "U21") (pin "2") (pinfunction "GND_2") (pintype "power_in"))
      (node (ref "U21") (pin "9") (pinfunction "EP_9") (pintype "power_in"))
      (node (ref "U31") (pin "4") (pinfunction "GND_4") (pintype "power_in"))
      (node (ref "U31") (pin "9") (pinfunction "GND_9") (pintype "power_in"))
      (node (ref "U32") (pin "2") (pinfunction "MODE_2") (pintype "input"))
      (node (ref "U32") (pin "6") (pinfunction "GND_6") (pintype "power_in"))
      (node (ref "U32") (pin "7") (pinfunction "Exposed_Thermal_Pad_7") (pintype "passive"))
      (node (ref "U33") (pin "4") (pinfunction "GND_4") (pintype "power_in"))
      (node (ref "U33") (pin "9") (pinfunction "GND_9") (pintype "power_in"))
      (node (ref "U8") (pin "2") (pinfunction "MODE_2") (pintype "input"))
      (node (ref "U8") (pin "6") (pinfunction "GND_6") (pintype "power_in"))
      (node (ref "U8") (pin "7") (pinfunction "Exposed_Thermal_Pad_7") (pintype "passive"))
      (node (ref "U9") (pin "4") (pinfunction "GND_4") (pintype "power_in"))
      (node (ref "U9") (pin "9") (pinfunction "GND_9") (pintype "power_in"))
    )
    (net (code "22") (name "Net-(C50-Input)") (class "Default")
      (node (ref "C50") (pin "1") (pinfunction "Input_1") (pintype "passive"))
      (node (ref "C51") (pin "1") (pinfunction "1_1") (pintype "passive"))
      (node (ref "L2") (pin "2") (pinfunction "2_2") (pintype "passive"))
      (node (ref "R37") (pin "2") (pinfunction "2_2") (pintype "passive"))
      (node (ref "U11") (pin "4") (pinfunction "FB1_4") (pintype "input"))
    )
    (net (code "23") (name "Net-(C50-Output)") (class "Default")
      (node (ref "C50") (pin "3") (pinfunction "Output_3") (pintype "passive"))
      (node (ref "C52") (pin "1") (pinfunction "1_1") (pintype "passive"))
      (node (ref "C55") (pin "2") (pinfunction "2_2") (pintype "passive"))
      (node (ref "U10") (pin "1") (pinfunction "EN_1") (pintype "input"))
      (node (ref "U10") (pin "2") (pinfunction "IN_2") (pintype "power_in"))
    )
    (net (code "24") (name "Net-(C85-Input)") (class "Default")
      (node (ref "C85") (pin "1") (pinfunction "Input_1") (pintype "passive"))
      (node (ref "C86") (pin "1") (pinfunction "1_1") (pintype "passive"))
      (node (ref "L4") (pin "2") (pinfunction "2_2") (pintype "passive"))
      (node (ref "R51") (pin "2") (pinfunction "2_2") (pintype "passive"))
      (node (ref "U16") (pin "4") (pinfunction "FB1_4") (pintype "input"))
    )
    (net (code "25") (name "Net-(C85-Output)") (class "Default")
      (node (ref "C85") (pin "3") (pinfunction "Output_3") (pintype "passive"))
      (node (ref "C87") (pin "1") (pinfunction "1_1") (pintype "passive"))
      (node (ref "C90") (pin "2") (pinfunction "2_2") (pintype "passive"))
      (node (ref "U15") (pin "1") (pinfunction "EN_1") (pintype "input"))
      (node (ref "U15") (pin "2") (pinfunction "IN_2") (pintype "power_in"))
    )
    (net (code "26") (name "Net-(D2-A)") (class "Default")
      (node (ref "D2") (pin "2") (pinfunction "A_2") (pintype "passive"))
      (node (ref "R34") (pin "1") (pinfunction "1_1") (pintype "passive"))
    )
    (net (code "27") (name "Net-(FB8-Input)") (class "Default")
      (node (ref "C34") (pin "1") (pinfunction "1_1") (pintype "passive"))
      (node (ref "C46") (pin "2") (pinfunction "2_2") (pintype "passive"))
      (node (ref "FB8") (pin "1") (pinfunction "Input_1") (pintype "passive"))
      (node (ref "L1") (pin "2") (pinfunction "2_2") (pintype "passive"))
      (node (ref "R32") (pin "2") (pinfunction "2_2") (pintype "passive"))
    )
    (net (code "28") (name "Net-(FB8-Output)") (class "Default")
      (node (ref "C37") (pin "2") (pinfunction "2_2") (pintype "passive"))
      (node (ref "C39") (pin "2") (pinfunction "2_2") (pintype "passive"))
      (node (ref "FB8") (pin "3") (pinfunction "Output_3") (pintype "passive"))
      (node (ref "U9") (pin "5") (pinfunction "EN_5") (pintype "input"))
      (node (ref "U9") (pin "7") (pinfunction "IN_7") (pintype "power_in"))
      (node (ref "U9") (pin "8") (pinfunction "IN_8") (pintype "power_in"))
    )
    (net (code "29") (name "Net-(FB9-Input)") (class "Default")
      (node (ref "C61") (pin "1") (pinfunction "1_1") (pintype "passive"))
      (node (ref "FB9") (pin "1") (pinfunction "Input_1") (pintype "passive"))
      (node (ref "L3") (pin "2") (pinfunction "2_2") (pintype "passive"))
      (node (ref "R39") (pin "2") (pinfunction "2_2") (pintype "passive"))
    )
    (net (code "30") (name "Net-(FB14-Input)") (class "Default")
      (node (ref "C96") (pin "1") (pinfunction "1_1") (pintype "passive"))
      (node (ref "FB14") (pin "1") (pinfunction "Input_1") (pintype "passive"))
      (node (ref "L5") (pin "2") (pinfunction "2_2") (pintype "passive"))
      (node (ref "R53") (pin "2") (pinfunction "2_2") (pintype "passive"))
    )
    (net (code "31") (name "Net-(FB24-Input)") (class "Default")
      (node (ref "C295") (pin "1") (pinfunction "1_1") (pintype "passive"))
      (node (ref "C299") (pin "2") (pinfunction "2_2") (pintype "passive"))
      (node (ref "FB24") (pin "1") (pinfunction "Input_1") (pintype "passive"))
      (node (ref "L70") (pin "2") (pinfunction "2_2") (pintype "passive"))
      (node (ref "R107") (pin "2") (pinfunction "2_2") (pintype "passive"))
    )
    (net (code "32") (name "Net-(FB24-Output)") (class "Default")
      (node (ref "C291") (pin "2") (pinfunction "2_2") (pintype "passive"))
      (node (ref "C293") (pin "2") (pinfunction "2_2") (pintype "passive"))
      (node (ref "C302") (pin "2") (pinfunction "2_2") (pintype "passive"))
      (node (ref "C304") (pin "2") (pinfunction "2_2") (pintype "passive"))
      (node (ref "FB24") (pin "3") (pinfunction "Output_3") (pintype "passive"))
      (node (ref "U31") (pin "5") (pinfunction "EN_5") (pintype "input"))
      (node (ref "U31") (pin "7") (pinfunction "IN_7") (pintype "power_in"))
      (node (ref "U31") (pin "8") (pinfunction "IN_8") (pintype "power_in"))
      (node (ref "U33") (pin "5") (pinfunction "EN_5") (pintype "input"))
      (node (ref "U33") (pin "7") (pinfunction "IN_7") (pintype "power_in"))
      (node (ref "U33") (pin "8") (pinfunction "IN_8") (pintype "power_in"))
    )
    (net (code "33") (name "Net-(Q1-G)") (class "Default")
      (node (ref "Q1") (pin "4") (pinfunction "G_4") (pintype "passive"))
      (node (ref "U14") (pin "4") (pinfunction "GATE_4") (pintype "output"))
    )
    (net (code "34") (name "Net-(U8-FB)") (class "Default")
      (node (ref "C34") (pin "2") (pinfunction "2_2") (pintype "passive"))
      (node (ref "R32") (pin "1") (pinfunction "1_1") (pintype "passive"))
      (node (ref "R36") (pin "2") (pinfunction "2_2") (pintype "passive"))
      (node (ref "U8") (pin "3") (pinfunction "FB_3") (pintype "input"))
    )
    (net (code "35") (name "Net-(U8-SW)") (class "Default")
      (node (ref "L1") (pin "1") (pinfunction "1_1") (pintype "passive"))
      (node (ref "U8") (pin "1") (pinfunction "SW_1") (pintype "passive"))
    )
    (net (code "36") (name "Net-(U9-FB)") (class "Default")
      (node (ref "R33") (pin "1") (pinfunction "1_1") (pintype "passive"))
      (node (ref "R35") (pin "2") (pinfunction "2_2") (pintype "passive"))
      (node (ref "U9") (pin "3") (pinfunction "FB_3") (pintype "input"))
    )
    (net (code "37") (name "Net-(U9-NR)") (class "Default")
      (node (ref "C44") (pin "1") (pinfunction "1_1") (pintype "passive"))
      (node (ref "U9") (pin "6") (pinfunction "NR_6") (pintype "passive"))
    )
    (net (code "38") (name "Net-(U10-NR)") (class "Default")
      (node (ref "C281") (pin "1") (pinfunction "1_1") (pintype "passive"))
      (node (ref "U10") (pin "5") (pinfunction "NR_5") (pintype "passive"))
    )
    (net (code "39") (name "Net-(U11-ADJ2)") (class "Default")
      (node (ref "R39") (pin "1") (pinfunction "1_1") (pintype "passive"))
      (node (ref "R41") (pin "2") (pinfunction "2_2") (pintype "passive"))
      (node (ref "U11") (pin "1") (pinfunction "ADJ2_1") (pintype "input"))
    )
    (net (code "40") (name "Net-(U11-SW1)") (class "Default")
      (node (ref "L2") (pin "1") (pinfunction "1_1") (pintype "passive"))
      (node (ref "U11") (pin "6") (pinfunction "SW1_6") (pintype "power_in"))
    )
    (net (code "41") (name "Net-(U11-SW2)") (class "Default")
      (node (ref "L3") (pin "1") (pinfunction "1_1") (pintype "passive"))
      (node (ref "U11") (pin "10") (pinfunction "SW2_10") (pintype "power_in"))
    )
    (net (code "42") (name "Net-(U12-FB)") (class "Default")
      (node (ref "R40") (pin "1") (pinfunction "1_1") (pintype "passive"))
      (node (ref "R42") (pin "2") (pinfunction "2_2") (pintype "passive"))
      (node (ref "U12") (pin "4") (pinfunction "FB_4") (pintype "input"))
    )
    (net (code "43") (name "Net-(U12-OUT)") (class "Default")
      (node (ref "C64") (pin "2") (pinfunction "2_2") (pintype "passive"))
      (node (ref "C65") (pin "1") (pinfunction "1_1") (pintype "passive"))
      (node (ref "C68") (pin "2") (pinfunction "2_2") (pintype "passive"))
      (node (ref "FB10") (pin "1") (pinfunction "1_1") (pintype "passive"))
      (node (ref "R40") (pin "2") (pinfunction "2_2") (pintype "passive"))
      (node (ref "U12") (pin "5") (pinfunction "OUT_5") (pintype "power_in"))
    )
    (net (code "44") (name "Net-(U13-FB)") (class "Default")
      (node (ref "R43") (pin "1") (pinfunction "1_1") (pintype "passive"))
      (node (ref "R44") (pin "2") (pinfunction "2_2") (pintype "passive"))
      (node (ref "U13") (pin "4") (pinfunction "FB_4") (pintype "input"))
    )
    (net (code "45") (name "Net-(U13-OUT)") (class "Default")
      (node (ref "C71") (pin "2") (pinfunction "2_2") (pintype "passive"))
      (node (ref "C72") (pin "1") (pinfunction "1_1") (pintype "passive"))
      (node (ref "C75") (pin "2") (pinfunction "2_2") (pintype "passive"))
      (node (ref "FB13") (pin "1") (pinfunction "1_1") (pintype "passive"))
      (node (ref "R43") (pin "2") (pinfunction "2_2") (pintype "passive"))
      (node (ref "U13") (pin "5") (pinfunction "OUT_5") (pintype "power_in"))
    )
    (net (code "46") (name "Net-(U15-NR)") (class "Default")
      (node (ref "C282") (pin "1") (pinfunction "1_1") (pintype "passive"))
      (node (ref "U15") (pin "5") (pinfunction "NR_5") (pintype "passive"))
    )
    (net (code "47") (name "Net-(U16-ADJ2)") (class "Default")
      (node (ref "R53") (pin "1") (pinfunction "1_1") (pintype "passive"))
      (node (ref "R55") (pin "2") (pinfunction "2_2") (pintype "passive"))
      (node (ref "U16") (pin "1") (pinfunction "ADJ2_1") (pintype "input"))
    )
    (net (code "48") (name "Net-(U16-SW1)") (class "Default")
      (node (ref "L4") (pin "1") (pinfunction "1_1") (pintype "passive"))
      (node (ref "U16") (pin "6") (pinfunction "SW1_6") (pintype "power_in"))
    )
    (net (code "49") (name "Net-(U16-SW2)") (class "Default")
      (node (ref "L5") (pin "1") (pinfunction "1_1") (pintype "passive"))
      (node (ref "U16") (pin "10") (pinfunction "SW2_10") (pintype "power_in"))
    )
    (net (code "50") (name "Net-(U17-FB)") (class "Default")
      (node (ref "R54") (pin "1") (pinfunction "1_1") (pintype "passive"))
      (node (ref "R56") (pin "2") (pinfunction "2_2") (pintype "passive"))
      (node (ref "U17") (pin "4") (pinfunction "FB_4") (pintype "input"))
    )
    (net (code "51") (name "Net-(U17-OUT)") (class "Default")
      (node (ref "C100") (pin "1") (pinfunction "1_1") (pintype "passive"))
      (node (ref "C103") (pin "2") (pinfunction "2_2") (pintype "passive"))
      (node (ref "C99") (pin "2") (pinfunction "2_2") (pintype "passive"))
      (node (ref "FB15") (pin "1") (pinfunction "1_1") (pintype "passive"))
      (node (ref "R54") (pin "2") (pinfunction "2_2") (pintype "passive"))
      (node (ref "U17") (pin "5") (pinfunction "OUT_5") (pintype "power_in"))
    )
    (net (code "52") (name "Net-(U18-FB)") (class "Default")
      (node (ref "R57") (pin "1") (pinfunction "1_1") (pintype "passive"))
      (node (ref "R58") (pin "2") (pinfunction "2_2") (pintype "passive"))
      (node (ref "U18") (pin "4") (pinfunction "FB_4") (pintype "input"))
    )
    (net (code "53") (name "Net-(U18-OUT)") (class "Default")
      (node (ref "C106") (pin "2") (pinfunction "2_2") (pintype "passive"))
      (node (ref "C107") (pin "1") (pinfunction "1_1") (pintype "passive"))
      (node (ref "C110") (pin "2") (pinfunction "2_2") (pintype "passive"))
      (node (ref "FB16") (pin "1") (pinfunction "1_1") (pintype "passive"))
      (node (ref "R57") (pin "2") (pinfunction "2_2") (pintype "passive"))
      (node (ref "U18") (pin "5") (pinfunction "OUT_5") (pintype "power_in"))
    )
    (net (code "54") (name "Net-(U19-SS)") (class "Default")
      (node (ref "C115") (pin "1") (pinfunction "1_1") (pintype "passive"))
      (node (ref "U19") (pin "8") (pinfunction "SS_8") (pintype "input"))
    )
    (net (code "55") (name "Net-(U20-SS)") (class "Default")
      (node (ref "C123") (pin "1") (pinfunction "1_1") (pintype "passive"))
      (node (ref "U20") (pin "8") (pinfunction "SS_8") (pintype "input"))
    )
    (net (code "56") (name "Net-(U21-SS)") (class "Default")
      (node (ref "C141") (pin "1") (pinfunction "1_1") (pintype "passive"))
      (node (ref "U21") (pin "8") (pinfunction "SS_8") (pintype "input"))
    )
    (net (code "57") (name "Net-(U31-FB)") (class "Default")
      (node (ref "R105") (pin "1") (pinfunction "1_1") (pintype "passive"))
      (node (ref "R106") (pin "2") (pinfunction "2_2") (pintype "passive"))
      (node (ref "U31") (pin "3") (pinfunction "FB_3") (pintype "input"))
    )
    (net (code "58") (name "Net-(U31-NR)") (class "Default")
      (node (ref "C294") (pin "1") (pinfunction "1_1") (pintype "passive"))
      (node (ref "U31") (pin "6") (pinfunction "NR_6") (pintype "passive"))
    )
    (net (code "59") (name "Net-(U32-FB)") (class "Default")
      (node (ref "C295") (pin "2") (pinfunction "2_2") (pintype "passive"))
      (node (ref "R107") (pin "1") (pinfunction "1_1") (pintype "passive"))
      (node (ref "R108") (pin "2") (pinfunction "2_2") (pintype "passive"))
      (node (ref "U32") (pin "3") (pinfunction "FB_3") (pintype "input"))
    )
    (net (code "60") (name "Net-(U32-SW)") (class "Default")
      (node (ref "L70") (pin "1") (pinfunction "1_1") (pintype "passive"))
      (node (ref "U32") (pin "1") (pinfunction "SW_1") (pintype "passive"))
    )
    (net (code "61") (name "Net-(U33-FB)") (class "Default")
      (node (ref "R109") (pin "1") (pinfunction "1_1") (pintype "passive"))
      (node (ref "R110") (pin "2") (pinfunction "2_2") (pintype "passive"))
      (node (ref "U33") (pin "3") (pinfunction "FB_3") (pintype "input"))
    )
    (net (code "62") (name "Net-(U33-NR)") (class "Default")
      (node (ref "C305") (pin "1") (pinfunction "1_1") (pintype "passive"))
      (node (ref "U33") (pin "6") (pinfunction "NR_6") (pintype "passive"))
    )
  )
)
